# USB_SATA.net
KiCad netlist of a schematic drawn in Altium Designer
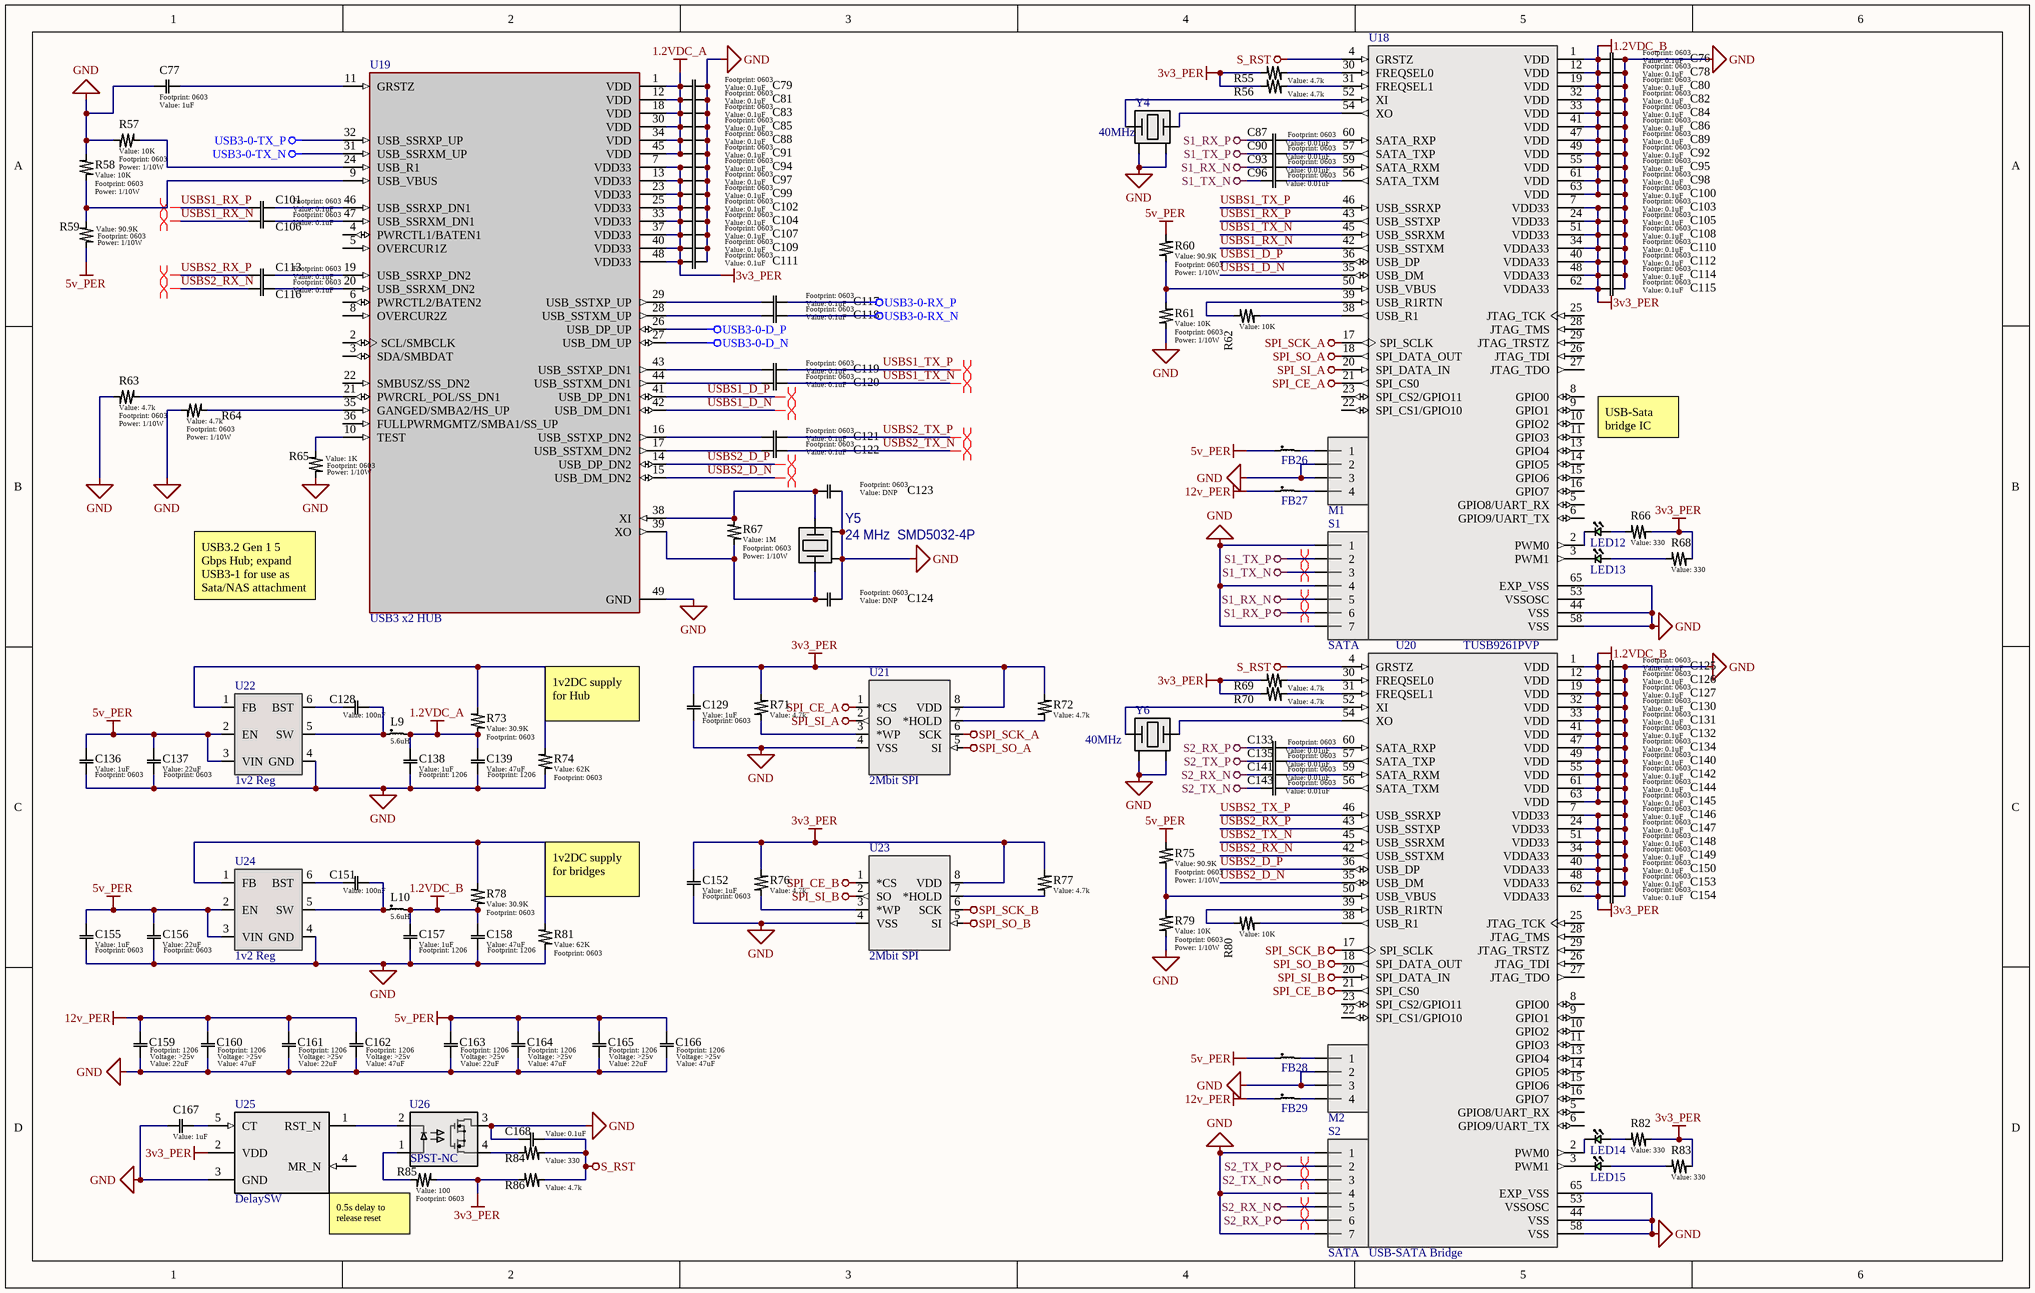
[diagram p0: USB_SATA.SchDoc]

(export (version "E")
  (design (tool "Eeschema 10.0.6"))
  (components
    (comp (ref "C76")
      (value "0.1uF")
      (footprint "0603")
      (fields
        (field (name "VOLTAGE") "10V")
        (field (name "TOLERANCE") "10%")
        (field (name "Comment") "Generic Capacitor")
      )
      (libsource (lib "Capacitors") (part "Generic Capacitor"))
    )
    (comp (ref "C77")
      (value "1uF")
      (footprint "0603")
      (fields
        (field (name "VOLTAGE") ">10V")
        (field (name "TOLERANCE") "10%")
        (field (name "Comment") "Generic Capacitor")
      )
      (libsource (lib "Capacitors") (part "Generic Capacitor"))
    )
    (comp (ref "C78")
      (value "0.1uF")
      (footprint "0603")
      (fields
        (field (name "VOLTAGE") "10V")
        (field (name "TOLERANCE") "10%")
        (field (name "Comment") "Generic Capacitor")
      )
      (libsource (lib "Capacitors") (part "Generic Capacitor"))
    )
    (comp (ref "C79")
      (value "0.1uF")
      (footprint "0603")
      (fields
        (field (name "VOLTAGE") "10V")
        (field (name "TOLERANCE") "10%")
        (field (name "Comment") "Generic Capacitor")
      )
      (libsource (lib "Capacitors") (part "Generic Capacitor"))
    )
    (comp (ref "C80")
      (value "0.1uF")
      (footprint "0603")
      (fields
        (field (name "VOLTAGE") "10V")
        (field (name "TOLERANCE") "10%")
        (field (name "Comment") "Generic Capacitor")
      )
      (libsource (lib "Capacitors") (part "Generic Capacitor"))
    )
    (comp (ref "C81")
      (value "0.1uF")
      (footprint "0603")
      (fields
        (field (name "VOLTAGE") "10V")
        (field (name "TOLERANCE") "10%")
        (field (name "Comment") "Generic Capacitor")
      )
      (libsource (lib "Capacitors") (part "Generic Capacitor"))
    )
    (comp (ref "C82")
      (value "0.1uF")
      (footprint "0603")
      (fields
        (field (name "VOLTAGE") "10V")
        (field (name "TOLERANCE") "10%")
        (field (name "Comment") "Generic Capacitor")
      )
      (libsource (lib "Capacitors") (part "Generic Capacitor"))
    )
    (comp (ref "C83")
      (value "0.1uF")
      (footprint "0603")
      (fields
        (field (name "VOLTAGE") "10V")
        (field (name "TOLERANCE") "10%")
        (field (name "Comment") "Generic Capacitor")
      )
      (libsource (lib "Capacitors") (part "Generic Capacitor"))
    )
    (comp (ref "C84")
      (value "0.1uF")
      (footprint "0603")
      (fields
        (field (name "VOLTAGE") "10V")
        (field (name "TOLERANCE") "10%")
        (field (name "Comment") "Generic Capacitor")
      )
      (libsource (lib "Capacitors") (part "Generic Capacitor"))
    )
    (comp (ref "C85")
      (value "0.1uF")
      (footprint "0603")
      (fields
        (field (name "VOLTAGE") "10V")
        (field (name "TOLERANCE") "10%")
        (field (name "Comment") "Generic Capacitor")
      )
      (libsource (lib "Capacitors") (part "Generic Capacitor"))
    )
    (comp (ref "C86")
      (value "0.1uF")
      (footprint "0603")
      (fields
        (field (name "VOLTAGE") "10V")
        (field (name "TOLERANCE") "10%")
        (field (name "Comment") "Generic Capacitor")
      )
      (libsource (lib "Capacitors") (part "Generic Capacitor"))
    )
    (comp (ref "C87")
      (value "0.01uF")
      (footprint "0603")
      (fields
        (field (name "VOLTAGE") "10V")
        (field (name "TOLERANCE") "10%")
        (field (name "Comment") "Generic Capacitor")
      )
      (libsource (lib "Capacitors") (part "Generic Capacitor"))
    )
    (comp (ref "C88")
      (value "0.1uF")
      (footprint "0603")
      (fields
        (field (name "VOLTAGE") "10V")
        (field (name "TOLERANCE") "10%")
        (field (name "Comment") "Generic Capacitor")
      )
      (libsource (lib "Capacitors") (part "Generic Capacitor"))
    )
    (comp (ref "C89")
      (value "0.1uF")
      (footprint "0603")
      (fields
        (field (name "VOLTAGE") "10V")
        (field (name "TOLERANCE") "10%")
        (field (name "Comment") "Generic Capacitor")
      )
      (libsource (lib "Capacitors") (part "Generic Capacitor"))
    )
    (comp (ref "C90")
      (value "0.01uF")
      (footprint "0603")
      (fields
        (field (name "VOLTAGE") "10V")
        (field (name "TOLERANCE") "10%")
        (field (name "Comment") "Generic Capacitor")
      )
      (libsource (lib "Capacitors") (part "Generic Capacitor"))
    )
    (comp (ref "C91")
      (value "0.1uF")
      (footprint "0603")
      (fields
        (field (name "VOLTAGE") "10V")
        (field (name "TOLERANCE") "10%")
        (field (name "Comment") "Generic Capacitor")
      )
      (libsource (lib "Capacitors") (part "Generic Capacitor"))
    )
    (comp (ref "C92")
      (value "0.1uF")
      (footprint "0603")
      (fields
        (field (name "VOLTAGE") "10V")
        (field (name "TOLERANCE") "10%")
        (field (name "Comment") "Generic Capacitor")
      )
      (libsource (lib "Capacitors") (part "Generic Capacitor"))
    )
    (comp (ref "C93")
      (value "0.01uF")
      (footprint "0603")
      (fields
        (field (name "VOLTAGE") "10V")
        (field (name "TOLERANCE") "10%")
        (field (name "Comment") "Generic Capacitor")
      )
      (libsource (lib "Capacitors") (part "Generic Capacitor"))
    )
    (comp (ref "C94")
      (value "0.1uF")
      (footprint "0603")
      (fields
        (field (name "VOLTAGE") "10V")
        (field (name "TOLERANCE") "10%")
        (field (name "Comment") "Generic Capacitor")
      )
      (libsource (lib "Capacitors") (part "Generic Capacitor"))
    )
    (comp (ref "C95")
      (value "0.1uF")
      (footprint "0603")
      (fields
        (field (name "VOLTAGE") "10V")
        (field (name "TOLERANCE") "10%")
        (field (name "Comment") "Generic Capacitor")
      )
      (libsource (lib "Capacitors") (part "Generic Capacitor"))
    )
    (comp (ref "C96")
      (value "0.01uF")
      (footprint "0603")
      (fields
        (field (name "VOLTAGE") "10V")
        (field (name "TOLERANCE") "10%")
        (field (name "Comment") "Generic Capacitor")
      )
      (libsource (lib "Capacitors") (part "Generic Capacitor"))
    )
    (comp (ref "C97")
      (value "0.1uF")
      (footprint "0603")
      (fields
        (field (name "VOLTAGE") "10V")
        (field (name "TOLERANCE") "10%")
        (field (name "Comment") "Generic Capacitor")
      )
      (libsource (lib "Capacitors") (part "Generic Capacitor"))
    )
    (comp (ref "C98")
      (value "0.1uF")
      (footprint "0603")
      (fields
        (field (name "VOLTAGE") "10V")
        (field (name "TOLERANCE") "10%")
        (field (name "Comment") "Generic Capacitor")
      )
      (libsource (lib "Capacitors") (part "Generic Capacitor"))
    )
    (comp (ref "C99")
      (value "0.1uF")
      (footprint "0603")
      (fields
        (field (name "VOLTAGE") "10V")
        (field (name "TOLERANCE") "10%")
        (field (name "Comment") "Generic Capacitor")
      )
      (libsource (lib "Capacitors") (part "Generic Capacitor"))
    )
    (comp (ref "C100")
      (value "0.1uF")
      (footprint "0603")
      (fields
        (field (name "VOLTAGE") "10V")
        (field (name "TOLERANCE") "10%")
        (field (name "Comment") "Generic Capacitor")
      )
      (libsource (lib "Capacitors") (part "Generic Capacitor"))
    )
    (comp (ref "C101")
      (value "0.1uF")
      (footprint "0603")
      (fields
        (field (name "VOLTAGE") "10V")
        (field (name "TOLERANCE") "10%")
        (field (name "Comment") "Generic Capacitor")
      )
      (libsource (lib "Capacitors") (part "Generic Capacitor"))
    )
    (comp (ref "C102")
      (value "0.1uF")
      (footprint "0603")
      (fields
        (field (name "VOLTAGE") "10V")
        (field (name "TOLERANCE") "10%")
        (field (name "Comment") "Generic Capacitor")
      )
      (libsource (lib "Capacitors") (part "Generic Capacitor"))
    )
    (comp (ref "C103")
      (value "0.1uF")
      (footprint "0603")
      (fields
        (field (name "VOLTAGE") "10V")
        (field (name "TOLERANCE") "10%")
        (field (name "Comment") "Generic Capacitor")
      )
      (libsource (lib "Capacitors") (part "Generic Capacitor"))
    )
    (comp (ref "C104")
      (value "0.1uF")
      (footprint "0603")
      (fields
        (field (name "VOLTAGE") "10V")
        (field (name "TOLERANCE") "10%")
        (field (name "Comment") "Generic Capacitor")
      )
      (libsource (lib "Capacitors") (part "Generic Capacitor"))
    )
    (comp (ref "C105")
      (value "0.1uF")
      (footprint "0603")
      (fields
        (field (name "VOLTAGE") "10V")
        (field (name "TOLERANCE") "10%")
        (field (name "Comment") "Generic Capacitor")
      )
      (libsource (lib "Capacitors") (part "Generic Capacitor"))
    )
    (comp (ref "C106")
      (value "0.1uF")
      (footprint "0603")
      (fields
        (field (name "VOLTAGE") "10V")
        (field (name "TOLERANCE") "10%")
        (field (name "Comment") "Generic Capacitor")
      )
      (libsource (lib "Capacitors") (part "Generic Capacitor"))
    )
    (comp (ref "C107")
      (value "0.1uF")
      (footprint "0603")
      (fields
        (field (name "VOLTAGE") "10V")
        (field (name "TOLERANCE") "10%")
        (field (name "Comment") "Generic Capacitor")
      )
      (libsource (lib "Capacitors") (part "Generic Capacitor"))
    )
    (comp (ref "C108")
      (value "0.1uF")
      (footprint "0603")
      (fields
        (field (name "VOLTAGE") "10V")
        (field (name "TOLERANCE") "10%")
        (field (name "Comment") "Generic Capacitor")
      )
      (libsource (lib "Capacitors") (part "Generic Capacitor"))
    )
    (comp (ref "C109")
      (value "0.1uF")
      (footprint "0603")
      (fields
        (field (name "VOLTAGE") "10V")
        (field (name "TOLERANCE") "10%")
        (field (name "Comment") "Generic Capacitor")
      )
      (libsource (lib "Capacitors") (part "Generic Capacitor"))
    )
    (comp (ref "C110")
      (value "0.1uF")
      (footprint "0603")
      (fields
        (field (name "VOLTAGE") "10V")
        (field (name "TOLERANCE") "10%")
        (field (name "Comment") "Generic Capacitor")
      )
      (libsource (lib "Capacitors") (part "Generic Capacitor"))
    )
    (comp (ref "C111")
      (value "0.1uF")
      (footprint "0603")
      (fields
        (field (name "VOLTAGE") "10V")
        (field (name "TOLERANCE") "10%")
        (field (name "Comment") "Generic Capacitor")
      )
      (libsource (lib "Capacitors") (part "Generic Capacitor"))
    )
    (comp (ref "C112")
      (value "0.1uF")
      (footprint "0603")
      (fields
        (field (name "VOLTAGE") "10V")
        (field (name "TOLERANCE") "10%")
        (field (name "Comment") "Generic Capacitor")
      )
      (libsource (lib "Capacitors") (part "Generic Capacitor"))
    )
    (comp (ref "C113")
      (value "0.1uF")
      (footprint "0603")
      (fields
        (field (name "VOLTAGE") "10V")
        (field (name "TOLERANCE") "10%")
        (field (name "Comment") "Generic Capacitor")
      )
      (libsource (lib "Capacitors") (part "Generic Capacitor"))
    )
    (comp (ref "C114")
      (value "0.1uF")
      (footprint "0603")
      (fields
        (field (name "VOLTAGE") "10V")
        (field (name "TOLERANCE") "10%")
        (field (name "Comment") "Generic Capacitor")
      )
      (libsource (lib "Capacitors") (part "Generic Capacitor"))
    )
    (comp (ref "C115")
      (value "0.1uF")
      (footprint "0603")
      (fields
        (field (name "VOLTAGE") "10V")
        (field (name "TOLERANCE") "10%")
        (field (name "Comment") "Generic Capacitor")
      )
      (libsource (lib "Capacitors") (part "Generic Capacitor"))
    )
    (comp (ref "C116")
      (value "0.1uF")
      (footprint "0603")
      (fields
        (field (name "VOLTAGE") "10V")
        (field (name "TOLERANCE") "10%")
        (field (name "Comment") "Generic Capacitor")
      )
      (libsource (lib "Capacitors") (part "Generic Capacitor"))
    )
    (comp (ref "C117")
      (value "0.1uF")
      (footprint "0603")
      (fields
        (field (name "VOLTAGE") "10V")
        (field (name "TOLERANCE") "10%")
        (field (name "Comment") "Generic Capacitor")
      )
      (libsource (lib "Capacitors") (part "Generic Capacitor"))
    )
    (comp (ref "C118")
      (value "0.1uF")
      (footprint "0603")
      (fields
        (field (name "VOLTAGE") "10V")
        (field (name "TOLERANCE") "10%")
        (field (name "Comment") "Generic Capacitor")
      )
      (libsource (lib "Capacitors") (part "Generic Capacitor"))
    )
    (comp (ref "C119")
      (value "0.1uF")
      (footprint "0603")
      (fields
        (field (name "VOLTAGE") "10V")
        (field (name "TOLERANCE") "10%")
        (field (name "Comment") "Generic Capacitor")
      )
      (libsource (lib "Capacitors") (part "Generic Capacitor"))
    )
    (comp (ref "C120")
      (value "0.1uF")
      (footprint "0603")
      (fields
        (field (name "VOLTAGE") "10V")
        (field (name "TOLERANCE") "10%")
        (field (name "Comment") "Generic Capacitor")
      )
      (libsource (lib "Capacitors") (part "Generic Capacitor"))
    )
    (comp (ref "C121")
      (value "0.1uF")
      (footprint "0603")
      (fields
        (field (name "VOLTAGE") "10V")
        (field (name "TOLERANCE") "10%")
        (field (name "Comment") "Generic Capacitor")
      )
      (libsource (lib "Capacitors") (part "Generic Capacitor"))
    )
    (comp (ref "C122")
      (value "0.1uF")
      (footprint "0603")
      (fields
        (field (name "VOLTAGE") "10V")
        (field (name "TOLERANCE") "10%")
        (field (name "Comment") "Generic Capacitor")
      )
      (libsource (lib "Capacitors") (part "Generic Capacitor"))
    )
    (comp (ref "C123")
      (value "DNP")
      (footprint "0603")
      (fields
        (field (name "VOLTAGE") ">10V")
        (field (name "TOLERANCE") "10%")
        (field (name "Comment") "Generic Capacitor")
      )
      (libsource (lib "Capacitors") (part "Generic Capacitor"))
    )
    (comp (ref "C124")
      (value "DNP")
      (footprint "0603")
      (fields
        (field (name "VOLTAGE") ">10V")
        (field (name "TOLERANCE") "10%")
        (field (name "Comment") "Generic Capacitor")
      )
      (libsource (lib "Capacitors") (part "Generic Capacitor"))
    )
    (comp (ref "C125")
      (value "0.1uF")
      (footprint "0603")
      (fields
        (field (name "VOLTAGE") "10V")
        (field (name "TOLERANCE") "10%")
        (field (name "Comment") "Generic Capacitor")
      )
      (libsource (lib "Capacitors") (part "Generic Capacitor"))
    )
    (comp (ref "C126")
      (value "0.1uF")
      (footprint "0603")
      (fields
        (field (name "VOLTAGE") "10V")
        (field (name "TOLERANCE") "10%")
        (field (name "Comment") "Generic Capacitor")
      )
      (libsource (lib "Capacitors") (part "Generic Capacitor"))
    )
    (comp (ref "C127")
      (value "0.1uF")
      (footprint "0603")
      (fields
        (field (name "VOLTAGE") "10V")
        (field (name "TOLERANCE") "10%")
        (field (name "Comment") "Generic Capacitor")
      )
      (libsource (lib "Capacitors") (part "Generic Capacitor"))
    )
    (comp (ref "C128")
      (value "100nF")
      (footprint "0603")
      (fields
        (field (name "VOLTAGE") ">10V")
        (field (name "TOLERANCE") "10%")
        (field (name "Comment") "Generic Capacitor")
      )
      (libsource (lib "Capacitors") (part "Generic Capacitor"))
    )
    (comp (ref "C129")
      (value "1uF")
      (footprint "0603")
      (fields
        (field (name "VOLTAGE") ">10V")
        (field (name "TOLERANCE") "10%")
        (field (name "Comment") "Generic Capacitor")
      )
      (libsource (lib "Capacitors") (part "Generic Capacitor"))
    )
    (comp (ref "C130")
      (value "0.1uF")
      (footprint "0603")
      (fields
        (field (name "VOLTAGE") "10V")
        (field (name "TOLERANCE") "10%")
        (field (name "Comment") "Generic Capacitor")
      )
      (libsource (lib "Capacitors") (part "Generic Capacitor"))
    )
    (comp (ref "C131")
      (value "0.1uF")
      (footprint "0603")
      (fields
        (field (name "VOLTAGE") "10V")
        (field (name "TOLERANCE") "10%")
        (field (name "Comment") "Generic Capacitor")
      )
      (libsource (lib "Capacitors") (part "Generic Capacitor"))
    )
    (comp (ref "C132")
      (value "0.1uF")
      (footprint "0603")
      (fields
        (field (name "VOLTAGE") "10V")
        (field (name "TOLERANCE") "10%")
        (field (name "Comment") "Generic Capacitor")
      )
      (libsource (lib "Capacitors") (part "Generic Capacitor"))
    )
    (comp (ref "C133")
      (value "0.01uF")
      (footprint "0603")
      (fields
        (field (name "VOLTAGE") "10V")
        (field (name "TOLERANCE") "10%")
        (field (name "Comment") "Generic Capacitor")
      )
      (libsource (lib "Capacitors") (part "Generic Capacitor"))
    )
    (comp (ref "C134")
      (value "0.1uF")
      (footprint "0603")
      (fields
        (field (name "VOLTAGE") "10V")
        (field (name "TOLERANCE") "10%")
        (field (name "Comment") "Generic Capacitor")
      )
      (libsource (lib "Capacitors") (part "Generic Capacitor"))
    )
    (comp (ref "C135")
      (value "0.01uF")
      (footprint "0603")
      (fields
        (field (name "VOLTAGE") "10V")
        (field (name "TOLERANCE") "10%")
        (field (name "Comment") "Generic Capacitor")
      )
      (libsource (lib "Capacitors") (part "Generic Capacitor"))
    )
    (comp (ref "C136")
      (value "1uF")
      (footprint "0603")
      (fields
        (field (name "VOLTAGE") ">10V")
        (field (name "TOLERANCE") "10%")
        (field (name "Comment") "Generic Capacitor")
      )
      (libsource (lib "Capacitors") (part "Generic Capacitor"))
    )
    (comp (ref "C137")
      (value "22uF")
      (footprint "0603")
      (fields
        (field (name "VOLTAGE") ">10V")
        (field (name "TOLERANCE") "10%")
        (field (name "Comment") "Generic Capacitor")
      )
      (libsource (lib "Capacitors") (part "Generic Capacitor"))
    )
    (comp (ref "C138")
      (value "1uF")
      (footprint "1206")
      (fields
        (field (name "VOLTAGE") ">10V")
        (field (name "TOLERANCE") "10%")
        (field (name "Comment") "Generic Capacitor")
      )
      (libsource (lib "Capacitors") (part "Generic Capacitor"))
    )
    (comp (ref "C139")
      (value "47uF")
      (footprint "1206")
      (fields
        (field (name "VOLTAGE") ">10V")
        (field (name "TOLERANCE") "10%")
        (field (name "Comment") "Generic Capacitor")
      )
      (libsource (lib "Capacitors") (part "Generic Capacitor"))
    )
    (comp (ref "C140")
      (value "0.1uF")
      (footprint "0603")
      (fields
        (field (name "VOLTAGE") "10V")
        (field (name "TOLERANCE") "10%")
        (field (name "Comment") "Generic Capacitor")
      )
      (libsource (lib "Capacitors") (part "Generic Capacitor"))
    )
    (comp (ref "C141")
      (value "0.01uF")
      (footprint "0603")
      (fields
        (field (name "VOLTAGE") "10V")
        (field (name "TOLERANCE") "10%")
        (field (name "Comment") "Generic Capacitor")
      )
      (libsource (lib "Capacitors") (part "Generic Capacitor"))
    )
    (comp (ref "C142")
      (value "0.1uF")
      (footprint "0603")
      (fields
        (field (name "VOLTAGE") "10V")
        (field (name "TOLERANCE") "10%")
        (field (name "Comment") "Generic Capacitor")
      )
      (libsource (lib "Capacitors") (part "Generic Capacitor"))
    )
    (comp (ref "C143")
      (value "0.01uF")
      (footprint "0603")
      (fields
        (field (name "VOLTAGE") "10V")
        (field (name "TOLERANCE") "10%")
        (field (name "Comment") "Generic Capacitor")
      )
      (libsource (lib "Capacitors") (part "Generic Capacitor"))
    )
    (comp (ref "C144")
      (value "0.1uF")
      (footprint "0603")
      (fields
        (field (name "VOLTAGE") "10V")
        (field (name "TOLERANCE") "10%")
        (field (name "Comment") "Generic Capacitor")
      )
      (libsource (lib "Capacitors") (part "Generic Capacitor"))
    )
    (comp (ref "C145")
      (value "0.1uF")
      (footprint "0603")
      (fields
        (field (name "VOLTAGE") "10V")
        (field (name "TOLERANCE") "10%")
        (field (name "Comment") "Generic Capacitor")
      )
      (libsource (lib "Capacitors") (part "Generic Capacitor"))
    )
    (comp (ref "C146")
      (value "0.1uF")
      (footprint "0603")
      (fields
        (field (name "VOLTAGE") "10V")
        (field (name "TOLERANCE") "10%")
        (field (name "Comment") "Generic Capacitor")
      )
      (libsource (lib "Capacitors") (part "Generic Capacitor"))
    )
    (comp (ref "C147")
      (value "0.1uF")
      (footprint "0603")
      (fields
        (field (name "VOLTAGE") "10V")
        (field (name "TOLERANCE") "10%")
        (field (name "Comment") "Generic Capacitor")
      )
      (libsource (lib "Capacitors") (part "Generic Capacitor"))
    )
    (comp (ref "C148")
      (value "0.1uF")
      (footprint "0603")
      (fields
        (field (name "VOLTAGE") "10V")
        (field (name "TOLERANCE") "10%")
        (field (name "Comment") "Generic Capacitor")
      )
      (libsource (lib "Capacitors") (part "Generic Capacitor"))
    )
    (comp (ref "C149")
      (value "0.1uF")
      (footprint "0603")
      (fields
        (field (name "VOLTAGE") "10V")
        (field (name "TOLERANCE") "10%")
        (field (name "Comment") "Generic Capacitor")
      )
      (libsource (lib "Capacitors") (part "Generic Capacitor"))
    )
    (comp (ref "C150")
      (value "0.1uF")
      (footprint "0603")
      (fields
        (field (name "VOLTAGE") "10V")
        (field (name "TOLERANCE") "10%")
        (field (name "Comment") "Generic Capacitor")
      )
      (libsource (lib "Capacitors") (part "Generic Capacitor"))
    )
    (comp (ref "C151")
      (value "100nF")
      (footprint "0603")
      (fields
        (field (name "VOLTAGE") ">10V")
        (field (name "TOLERANCE") "10%")
        (field (name "Comment") "Generic Capacitor")
      )
      (libsource (lib "Capacitors") (part "Generic Capacitor"))
    )
    (comp (ref "C152")
      (value "1uF")
      (footprint "0603")
      (fields
        (field (name "VOLTAGE") ">10V")
        (field (name "TOLERANCE") "10%")
        (field (name "Comment") "Generic Capacitor")
      )
      (libsource (lib "Capacitors") (part "Generic Capacitor"))
    )
    (comp (ref "C153")
      (value "0.1uF")
      (footprint "0603")
      (fields
        (field (name "VOLTAGE") "10V")
        (field (name "TOLERANCE") "10%")
        (field (name "Comment") "Generic Capacitor")
      )
      (libsource (lib "Capacitors") (part "Generic Capacitor"))
    )
    (comp (ref "C154")
      (value "0.1uF")
      (footprint "0603")
      (fields
        (field (name "VOLTAGE") "10V")
        (field (name "TOLERANCE") "10%")
        (field (name "Comment") "Generic Capacitor")
      )
      (libsource (lib "Capacitors") (part "Generic Capacitor"))
    )
    (comp (ref "C155")
      (value "1uF")
      (footprint "0603")
      (fields
        (field (name "VOLTAGE") ">10V")
        (field (name "TOLERANCE") "10%")
        (field (name "Comment") "Generic Capacitor")
      )
      (libsource (lib "Capacitors") (part "Generic Capacitor"))
    )
    (comp (ref "C156")
      (value "22uF")
      (footprint "0603")
      (fields
        (field (name "VOLTAGE") ">10V")
        (field (name "TOLERANCE") "10%")
        (field (name "Comment") "Generic Capacitor")
      )
      (libsource (lib "Capacitors") (part "Generic Capacitor"))
    )
    (comp (ref "C157")
      (value "1uF")
      (footprint "1206")
      (fields
        (field (name "VOLTAGE") ">10V")
        (field (name "TOLERANCE") "10%")
        (field (name "Comment") "Generic Capacitor")
      )
      (libsource (lib "Capacitors") (part "Generic Capacitor"))
    )
    (comp (ref "C158")
      (value "47uF")
      (footprint "1206")
      (fields
        (field (name "VOLTAGE") ">10V")
        (field (name "TOLERANCE") "10%")
        (field (name "Comment") "Generic Capacitor")
      )
      (libsource (lib "Capacitors") (part "Generic Capacitor"))
    )
    (comp (ref "C159")
      (value "22uF")
      (footprint "1206")
      (fields
        (field (name "VOLTAGE") ">25v")
        (field (name "TOLERANCE") "20%")
        (field (name "Comment") "Generic Capacitor")
      )
      (libsource (lib "Capacitors") (part "Generic Capacitor"))
    )
    (comp (ref "C160")
      (value "47uF")
      (footprint "1206")
      (fields
        (field (name "VOLTAGE") ">25v")
        (field (name "TOLERANCE") "20%")
        (field (name "Comment") "Generic Capacitor")
      )
      (libsource (lib "Capacitors") (part "Generic Capacitor"))
    )
    (comp (ref "C161")
      (value "22uF")
      (footprint "1206")
      (fields
        (field (name "VOLTAGE") ">25v")
        (field (name "TOLERANCE") "20%")
        (field (name "Comment") "Generic Capacitor")
      )
      (libsource (lib "Capacitors") (part "Generic Capacitor"))
    )
    (comp (ref "C162")
      (value "47uF")
      (footprint "1206")
      (fields
        (field (name "VOLTAGE") ">25v")
        (field (name "TOLERANCE") "20%")
        (field (name "Comment") "Generic Capacitor")
      )
      (libsource (lib "Capacitors") (part "Generic Capacitor"))
    )
    (comp (ref "C163")
      (value "22uF")
      (footprint "1206")
      (fields
        (field (name "VOLTAGE") ">25v")
        (field (name "TOLERANCE") "20%")
        (field (name "Comment") "Generic Capacitor")
      )
      (libsource (lib "Capacitors") (part "Generic Capacitor"))
    )
    (comp (ref "C164")
      (value "47uF")
      (footprint "1206")
      (fields
        (field (name "VOLTAGE") ">25v")
        (field (name "TOLERANCE") "20%")
        (field (name "Comment") "Generic Capacitor")
      )
      (libsource (lib "Capacitors") (part "Generic Capacitor"))
    )
    (comp (ref "C165")
      (value "22uF")
      (footprint "1206")
      (fields
        (field (name "VOLTAGE") ">25v")
        (field (name "TOLERANCE") "20%")
        (field (name "Comment") "Generic Capacitor")
      )
      (libsource (lib "Capacitors") (part "Generic Capacitor"))
    )
    (comp (ref "C166")
      (value "47uF")
      (footprint "1206")
      (fields
        (field (name "VOLTAGE") ">25v")
        (field (name "TOLERANCE") "20%")
        (field (name "Comment") "Generic Capacitor")
      )
      (libsource (lib "Capacitors") (part "Generic Capacitor"))
    )
    (comp (ref "C167")
      (value "1uF")
      (footprint "0603")
      (fields
        (field (name "VOLTAGE") "10V")
        (field (name "TOLERANCE") "10%")
        (field (name "Comment") "Generic Capacitor")
      )
      (libsource (lib "Capacitors") (part "Generic Capacitor"))
    )
    (comp (ref "C168")
      (value "0.1uF")
      (footprint "0603")
      (fields
        (field (name "VOLTAGE") "10V")
        (field (name "TOLERANCE") "10%")
        (field (name "Comment") "Generic Capacitor")
      )
      (libsource (lib "Capacitors") (part "Generic Capacitor"))
    )
    (comp (ref "FB26")
      (value "1206 Ferrite")
      (footprint "1206")
      (description "160 Ohms @ 100MHz 1 Power, Signal Line Ferrite Bead 1206 (3216 Metric) 6A 18mOhm")
      (libsource (lib "Inductors") (part "HI1206T161R-10"))
    )
    (comp (ref "FB27")
      (value "1206 Ferrite")
      (footprint "1206")
      (description "160 Ohms @ 100MHz 1 Power, Signal Line Ferrite Bead 1206 (3216 Metric) 6A 18mOhm")
      (libsource (lib "Inductors") (part "HI1206T161R-10"))
    )
    (comp (ref "FB28")
      (value "1206 Ferrite")
      (footprint "1206")
      (description "160 Ohms @ 100MHz 1 Power, Signal Line Ferrite Bead 1206 (3216 Metric) 6A 18mOhm")
      (libsource (lib "Inductors") (part "HI1206T161R-10"))
    )
    (comp (ref "FB29")
      (value "1206 Ferrite")
      (footprint "1206")
      (description "160 Ohms @ 100MHz 1 Power, Signal Line Ferrite Bead 1206 (3216 Metric) 6A 18mOhm")
      (libsource (lib "Inductors") (part "HI1206T161R-10"))
    )
    (comp (ref "L9")
      (value "5.6uH")
      (footprint "TMPC0402HP")
      (description "2A 5.6uH ±20% SMD Power Inductor")
      (libsource (lib "Inductors") (part "TMPC0402HP-5R6MG-Z02"))
    )
    (comp (ref "L10")
      (value "5.6uH")
      (footprint "TMPC0402HP")
      (description "2A 5.6uH ±20% SMD Power Inductor")
      (libsource (lib "Inductors") (part "TMPC0402HP-5R6MG-Z02"))
    )
    (comp (ref "LED12")
      (value "LTST-C191KGKT")
      (footprint "0603 (1608 Metric) Concave")
      (description "LED Uni-Color Green 574nm 2-Pin Chip LED T/R")
      (libsource (lib "Gamber - Johnson LLC") (part "LTST-C191KGKT"))
    )
    (comp (ref "LED13")
      (value "LTST-C191KGKT")
      (footprint "0603 (1608 Metric) Concave")
      (description "LED Uni-Color Green 574nm 2-Pin Chip LED T/R")
      (libsource (lib "Gamber - Johnson LLC") (part "LTST-C191KGKT"))
    )
    (comp (ref "LED14")
      (value "LTST-C191KGKT")
      (footprint "0603 (1608 Metric) Concave")
      (description "LED Uni-Color Green 574nm 2-Pin Chip LED T/R")
      (libsource (lib "Gamber - Johnson LLC") (part "LTST-C191KGKT"))
    )
    (comp (ref "LED15")
      (value "LTST-C191KGKT")
      (footprint "0603 (1608 Metric) Concave")
      (description "LED Uni-Color Green 574nm 2-Pin Chip LED T/R")
      (libsource (lib "Gamber - Johnson LLC") (part "LTST-C191KGKT"))
    )
    (comp (ref "M1")
      (value "MATE-n-Lock")
      (footprint "794287-1")
      (description "4 Position Header Connector 0.200\" (5.08mm) Through Hole Tin")
      (libsource (lib "Connectors") (part "794287-1"))
    )
    (comp (ref "M2")
      (value "MATE-n-Lock")
      (footprint "794287-1")
      (description "4 Position Header Connector 0.200\" (5.08mm) Through Hole Tin")
      (libsource (lib "Connectors") (part "794287-1"))
    )
    (comp (ref "R55")
      (value "4.7k")
      (footprint "0603")
      (fields
        (field (name "TOLERANCE") "1%")
        (field (name "POWER") "1/10W")
        (field (name "Comment") "Generic Resistor")
      )
      (libsource (lib "Resistors") (part "Generic Resistor"))
    )
    (comp (ref "R56")
      (value "4.7k")
      (footprint "0603")
      (fields
        (field (name "TOLERANCE") "1%")
        (field (name "POWER") "1/10W")
        (field (name "Comment") "Generic Resistor")
      )
      (libsource (lib "Resistors") (part "Generic Resistor"))
    )
    (comp (ref "R57")
      (value "10K")
      (footprint "0603")
      (fields
        (field (name "TOLERANCE") "1%")
        (field (name "POWER") "1/10W")
        (field (name "Comment") "Generic Resistor")
      )
      (libsource (lib "Resistors") (part "Generic Resistor"))
    )
    (comp (ref "R58")
      (value "10K")
      (footprint "0603")
      (fields
        (field (name "TOLERANCE") "1%")
        (field (name "POWER") "1/10W")
        (field (name "Comment") "Generic Resistor")
      )
      (libsource (lib "Resistors") (part "Generic Resistor"))
    )
    (comp (ref "R59")
      (value "90.9K")
      (footprint "0603")
      (fields
        (field (name "TOLERANCE") "1%")
        (field (name "POWER") "1/10W")
        (field (name "Comment") "Generic Resistor")
      )
      (libsource (lib "Resistors") (part "Generic Resistor"))
    )
    (comp (ref "R60")
      (value "90.9K")
      (footprint "0603")
      (fields
        (field (name "TOLERANCE") "1%")
        (field (name "POWER") "1/10W")
        (field (name "Comment") "Generic Resistor")
      )
      (libsource (lib "Resistors") (part "Generic Resistor"))
    )
    (comp (ref "R61")
      (value "10K")
      (footprint "0603")
      (fields
        (field (name "TOLERANCE") "1%")
        (field (name "POWER") "1/10W")
        (field (name "Comment") "Generic Resistor")
      )
      (libsource (lib "Resistors") (part "Generic Resistor"))
    )
    (comp (ref "R62")
      (value "10K")
      (footprint "0603")
      (fields
        (field (name "TOLERANCE") "1%")
        (field (name "POWER") "1/10W")
        (field (name "Comment") "Generic Resistor")
      )
      (libsource (lib "Resistors") (part "Generic Resistor"))
    )
    (comp (ref "R63")
      (value "4.7k")
      (footprint "0603")
      (fields
        (field (name "TOLERANCE") "1%")
        (field (name "POWER") "1/10W")
        (field (name "Comment") "Generic Resistor")
      )
      (libsource (lib "Resistors") (part "Generic Resistor"))
    )
    (comp (ref "R64")
      (value "4.7k")
      (footprint "0603")
      (fields
        (field (name "TOLERANCE") "1%")
        (field (name "POWER") "1/10W")
        (field (name "Comment") "Generic Resistor")
      )
      (libsource (lib "Resistors") (part "Generic Resistor"))
    )
    (comp (ref "R65")
      (value "1K")
      (footprint "0603")
      (fields
        (field (name "TOLERANCE") "1%")
        (field (name "POWER") "1/10W")
        (field (name "Comment") "Generic Resistor")
      )
      (libsource (lib "Resistors") (part "Generic Resistor"))
    )
    (comp (ref "R66")
      (value "330")
      (footprint "0603")
      (fields
        (field (name "TOLERANCE") "1%")
        (field (name "POWER") "1/10W")
        (field (name "Comment") "Generic Resistor")
      )
      (libsource (lib "Resistors") (part "Generic Resistor"))
    )
    (comp (ref "R67")
      (value "1M")
      (footprint "0603")
      (fields
        (field (name "TOLERANCE") "1%")
        (field (name "POWER") "1/10W")
        (field (name "Comment") "Generic Resistor")
      )
      (libsource (lib "Resistors") (part "Generic Resistor"))
    )
    (comp (ref "R68")
      (value "330")
      (footprint "0603")
      (fields
        (field (name "TOLERANCE") "1%")
        (field (name "POWER") "1/10W")
        (field (name "Comment") "Generic Resistor")
      )
      (libsource (lib "Resistors") (part "Generic Resistor"))
    )
    (comp (ref "R69")
      (value "4.7k")
      (footprint "0603")
      (fields
        (field (name "TOLERANCE") "1%")
        (field (name "POWER") "1/10W")
        (field (name "Comment") "Generic Resistor")
      )
      (libsource (lib "Resistors") (part "Generic Resistor"))
    )
    (comp (ref "R70")
      (value "4.7k")
      (footprint "0603")
      (fields
        (field (name "TOLERANCE") "1%")
        (field (name "POWER") "1/10W")
        (field (name "Comment") "Generic Resistor")
      )
      (libsource (lib "Resistors") (part "Generic Resistor"))
    )
    (comp (ref "R71")
      (value "4.7k")
      (footprint "0603")
      (fields
        (field (name "TOLERANCE") "1%")
        (field (name "POWER") "1/10W")
        (field (name "Comment") "Generic Resistor")
      )
      (libsource (lib "Resistors") (part "Generic Resistor"))
    )
    (comp (ref "R72")
      (value "4.7k")
      (footprint "0603")
      (fields
        (field (name "TOLERANCE") "1%")
        (field (name "POWER") "1/10W")
        (field (name "Comment") "Generic Resistor")
      )
      (libsource (lib "Resistors") (part "Generic Resistor"))
    )
    (comp (ref "R73")
      (value "30.9K")
      (footprint "0603")
      (fields
        (field (name "TOLERANCE") "1%")
        (field (name "POWER") "1/10W")
        (field (name "Comment") "Generic Resistor")
      )
      (libsource (lib "Resistors") (part "Generic Resistor"))
    )
    (comp (ref "R74")
      (value "62K")
      (footprint "0603")
      (fields
        (field (name "TOLERANCE") "1%")
        (field (name "POWER") "1/10W")
        (field (name "Comment") "Generic Resistor")
      )
      (libsource (lib "Resistors") (part "Generic Resistor"))
    )
    (comp (ref "R75")
      (value "90.9K")
      (footprint "0603")
      (fields
        (field (name "TOLERANCE") "1%")
        (field (name "POWER") "1/10W")
        (field (name "Comment") "Generic Resistor")
      )
      (libsource (lib "Resistors") (part "Generic Resistor"))
    )
    (comp (ref "R76")
      (value "4.7k")
      (footprint "0603")
      (fields
        (field (name "TOLERANCE") "1%")
        (field (name "POWER") "1/10W")
        (field (name "Comment") "Generic Resistor")
      )
      (libsource (lib "Resistors") (part "Generic Resistor"))
    )
    (comp (ref "R77")
      (value "4.7k")
      (footprint "0603")
      (fields
        (field (name "TOLERANCE") "1%")
        (field (name "POWER") "1/10W")
        (field (name "Comment") "Generic Resistor")
      )
      (libsource (lib "Resistors") (part "Generic Resistor"))
    )
    (comp (ref "R78")
      (value "30.9K")
      (footprint "0603")
      (fields
        (field (name "TOLERANCE") "1%")
        (field (name "POWER") "1/10W")
        (field (name "Comment") "Generic Resistor")
      )
      (libsource (lib "Resistors") (part "Generic Resistor"))
    )
    (comp (ref "R79")
      (value "10K")
      (footprint "0603")
      (fields
        (field (name "TOLERANCE") "1%")
        (field (name "POWER") "1/10W")
        (field (name "Comment") "Generic Resistor")
      )
      (libsource (lib "Resistors") (part "Generic Resistor"))
    )
    (comp (ref "R80")
      (value "10K")
      (footprint "0603")
      (fields
        (field (name "TOLERANCE") "1%")
        (field (name "POWER") "1/10W")
        (field (name "Comment") "Generic Resistor")
      )
      (libsource (lib "Resistors") (part "Generic Resistor"))
    )
    (comp (ref "R81")
      (value "62K")
      (footprint "0603")
      (fields
        (field (name "TOLERANCE") "1%")
        (field (name "POWER") "1/10W")
        (field (name "Comment") "Generic Resistor")
      )
      (libsource (lib "Resistors") (part "Generic Resistor"))
    )
    (comp (ref "R82")
      (value "330")
      (footprint "0603")
      (fields
        (field (name "TOLERANCE") "1%")
        (field (name "POWER") "1/10W")
        (field (name "Comment") "Generic Resistor")
      )
      (libsource (lib "Resistors") (part "Generic Resistor"))
    )
    (comp (ref "R83")
      (value "330")
      (footprint "0603")
      (fields
        (field (name "TOLERANCE") "1%")
        (field (name "POWER") "1/10W")
        (field (name "Comment") "Generic Resistor")
      )
      (libsource (lib "Resistors") (part "Generic Resistor"))
    )
    (comp (ref "R84")
      (value "330")
      (footprint "0603")
      (fields
        (field (name "TOLERANCE") "1%")
        (field (name "POWER") "1/10W")
        (field (name "Comment") "Generic Resistor")
      )
      (libsource (lib "Resistors") (part "Generic Resistor"))
    )
    (comp (ref "R85")
      (value "100")
      (footprint "0603")
      (fields
        (field (name "TOLERANCE") "1%")
        (field (name "POWER") "1/10W")
        (field (name "Comment") "Generic Resistor")
      )
      (libsource (lib "Resistors") (part "Generic Resistor"))
    )
    (comp (ref "R86")
      (value "4.7k")
      (footprint "0603")
      (fields
        (field (name "TOLERANCE") "1%")
        (field (name "POWER") "1/10W")
        (field (name "Comment") "Generic Resistor")
      )
      (libsource (lib "Resistors") (part "Generic Resistor"))
    )
    (comp (ref "S1")
      (value "SATA")
      (footprint "67800-8025")
      (description "7 Position SATA Header, Shrouded Connector Solder Through Hole")
      (libsource (lib "Connectors") (part "67800-8025"))
    )
    (comp (ref "S2")
      (value "SATA")
      (footprint "67800-8025")
      (description "7 Position SATA Header, Shrouded Connector Solder Through Hole")
      (libsource (lib "Connectors") (part "67800-8025"))
    )
    (comp (ref "U18")
      (value "USB-SATA Bridge")
      (footprint "64-HTQFP (7x7)")
      (description "HDD, CD, DVD Drive Interface 64-HTQFP _7x7_")
      (fields
        (field (name "MF") "Texas Instruments")
        (field (name "DIGI-KEY_PART_NUMBER") "296-28827-ND")
        (field (name "MP") "TUSB9261PVP")
      )
      (libsource (lib "Misc ICs") (part "TUSB9261PVP"))
    )
    (comp (ref "U19")
      (value "USB3 x2 HUB")
      (footprint "HTQFP-48(7x7)")
      (description "USB Hub Controller USB 3.0")
      (libsource (lib "Hub ICs") (part "TUSB8020BPHP"))
    )
    (comp (ref "U20")
      (value "USB-SATA Bridge")
      (footprint "64-HTQFP (7x7)")
      (description "HDD, CD, DVD Drive Interface 64-HTQFP _7x7_")
      (fields (field (name "MF") "Texas Instruments") (field (name "DIGI-KEY_PART_NUMBER") "296-28827-ND"))
      (libsource (lib "Misc ICs") (part "TUSB9261PVP"))
    )
    (comp (ref "U21")
      (value "2Mbit SPI")
      (footprint "8-SOIC (0.154\", 3.90mm Width)")
      (description "IC FLASH 2MBIT SPI 30MHZ 8SOP")
      (libsource (lib "Misc ICs") (part "LE25U20AMB-AH"))
    )
    (comp (ref "U22")
      (value "1v2 Reg")
      (footprint "TSOT-23-6")
      (description "Step-down type Adjustable 2A 1.2V~12V 3.8V~32V TSOT-23-6 DC-DC Converter")
      (libsource (lib "Regulators") (part "AP63201WU-7"))
    )
    (comp (ref "U23")
      (value "2Mbit SPI")
      (footprint "8-SOIC (0.154\", 3.90mm Width)")
      (description "IC FLASH 2MBIT SPI 30MHZ 8SOP")
      (libsource (lib "Misc ICs") (part "LE25U20AMB-AH"))
    )
    (comp (ref "U24")
      (value "1v2 Reg")
      (footprint "TSOT-23-6")
      (description "Step-down type Adjustable 2A 1.2V~12V 3.8V~32V TSOT-23-6 DC-DC Converter")
      (libsource (lib "Regulators") (part "AP63201WU-7"))
    )
    (comp (ref "U25")
      (value "DelaySW")
      (footprint "TSOT-23-5")
      (description "Supervisor Open Drain or Open Collector 1 Channel SOT-23-5\r\n2.2V Threshold")
      (libsource (lib "Switches") (part "TPS3840DL22DBVR"))
    )
    (comp (ref "U26")
      (value "SPST-NC")
      (footprint "4-SOP")
      (description "SSR RELAY SPST-NC 400MA 0-60V")
      (libsource (lib "Switches") (part "CPC1117N"))
    )
    (comp (ref "Y4")
      (value "40MHz")
      (footprint "SMD3225-4P")
      (description "40MHz Surface Mount Crystal 10pF ±10ppm SMD3225-4P Crystal")
      (libsource (lib "Clock ICs") (part "L327S400H11L"))
    )
    (comp (ref "Y5")
      (value "24 MHz  SMD5032-4P")
      (footprint "ECS-240-18-30BQ-DS")
      (description "24 MHz ±30ppm Crystal 18pF 30 Ohms 4-SMD, No Lead")
      (libsource (lib "Gamber - Johnson LLC") (part "ECS-240-18-30BQ-DS"))
    )
    (comp (ref "Y6")
      (value "40MHz")
      (footprint "SMD3225-4P")
      (description "40MHz Surface Mount Crystal 10pF ±10ppm SMD3225-4P Crystal")
      (libsource (lib "Clock ICs") (part "L327S400H11L"))
    )
  )
  (nets
    (net (code "1") (name "/USBS1_D_N") (class "Default")
      (node (ref "U18") (pin "35") (pinfunction "USB_DM_35") (pintype "bidirectional"))
      (node (ref "U19") (pin "42") (pinfunction "USB_DM_DN1_42") (pintype "bidirectional"))
    )
    (net (code "2") (name "/USBS1_D_P") (class "Default")
      (node (ref "U18") (pin "36") (pinfunction "USB_DP_36") (pintype "bidirectional"))
      (node (ref "U19") (pin "41") (pinfunction "USB_DP_DN1_41") (pintype "bidirectional"))
    )
    (net (code "3") (name "/USBS1_RX_N") (class "Default")
      (node (ref "C106") (pin "2") (pinfunction "2_2") (pintype "passive"))
      (node (ref "U18") (pin "42") (pinfunction "USB_SSTXM_42") (pintype "output"))
    )
    (net (code "4") (name "/USBS1_RX_P") (class "Default")
      (node (ref "C101") (pin "2") (pinfunction "2_2") (pintype "passive"))
      (node (ref "U18") (pin "43") (pinfunction "USB_SSTXP_43") (pintype "output"))
    )
    (net (code "5") (name "/USBS1_TX_N") (class "Default")
      (node (ref "C120") (pin "1") (pinfunction "1_1") (pintype "passive"))
      (node (ref "U18") (pin "45") (pinfunction "USB_SSRXM_45") (pintype "input"))
    )
    (net (code "6") (name "/USBS1_TX_P") (class "Default")
      (node (ref "C119") (pin "1") (pinfunction "1_1") (pintype "passive"))
      (node (ref "U18") (pin "46") (pinfunction "USB_SSRXP_46") (pintype "input"))
    )
    (net (code "7") (name "/USBS2_D_N") (class "Default")
      (node (ref "U19") (pin "15") (pinfunction "USB_DM_DN2_15") (pintype "bidirectional"))
      (node (ref "U20") (pin "35") (pinfunction "USB_DM_35") (pintype "bidirectional"))
    )
    (net (code "8") (name "/USBS2_D_P") (class "Default")
      (node (ref "U19") (pin "14") (pinfunction "USB_DP_DN2_14") (pintype "bidirectional"))
      (node (ref "U20") (pin "36") (pinfunction "USB_DP_36") (pintype "bidirectional"))
    )
    (net (code "9") (name "/USBS2_RX_N") (class "Default")
      (node (ref "C116") (pin "2") (pinfunction "2_2") (pintype "passive"))
      (node (ref "U20") (pin "42") (pinfunction "USB_SSTXM_42") (pintype "output"))
    )
    (net (code "10") (name "/USBS2_RX_P") (class "Default")
      (node (ref "C113") (pin "2") (pinfunction "2_2") (pintype "passive"))
      (node (ref "U20") (pin "43") (pinfunction "USB_SSTXP_43") (pintype "output"))
    )
    (net (code "11") (name "/USBS2_TX_N") (class "Default")
      (node (ref "C122") (pin "1") (pinfunction "1_1") (pintype "passive"))
      (node (ref "U20") (pin "45") (pinfunction "USB_SSRXM_45") (pintype "input"))
    )
    (net (code "12") (name "/USBS2_TX_P") (class "Default")
      (node (ref "C121") (pin "1") (pinfunction "1_1") (pintype "passive"))
      (node (ref "U20") (pin "46") (pinfunction "USB_SSRXP_46") (pintype "input"))
    )
    (net (code "13") (name "1.2VDC_A") (class "Default")
      (node (ref "C138") (pin "1") (pinfunction "1_1") (pintype "passive"))
      (node (ref "C139") (pin "1") (pinfunction "1_1") (pintype "passive"))
      (node (ref "C79") (pin "2") (pinfunction "2_2") (pintype "passive"))
      (node (ref "C81") (pin "2") (pinfunction "2_2") (pintype "passive"))
      (node (ref "C83") (pin "2") (pinfunction "2_2") (pintype "passive"))
      (node (ref "C85") (pin "2") (pinfunction "2_2") (pintype "passive"))
      (node (ref "C88") (pin "2") (pinfunction "2_2") (pintype "passive"))
      (node (ref "C91") (pin "2") (pinfunction "2_2") (pintype "passive"))
      (node (ref "L9") (pin "2") (pinfunction "2_2") (pintype "passive"))
      (node (ref "R73") (pin "1") (pinfunction "1_1") (pintype "passive"))
      (node (ref "U19") (pin "1") (pinfunction "VDD_1") (pintype "power_in"))
      (node (ref "U19") (pin "12") (pinfunction "VDD_12") (pintype "power_in"))
      (node (ref "U19") (pin "18") (pinfunction "VDD_18") (pintype "power_in"))
      (node (ref "U19") (pin "30") (pinfunction "VDD_30") (pintype "power_in"))
      (node (ref "U19") (pin "34") (pinfunction "VDD_34") (pintype "power_in"))
      (node (ref "U19") (pin "45") (pinfunction "VDD_45") (pintype "power_in"))
    )
    (net (code "14") (name "1.2VDC_B") (class "Default")
      (node (ref "C100") (pin "2") (pinfunction "2_2") (pintype "passive"))
      (node (ref "C125") (pin "2") (pinfunction "2_2") (pintype "passive"))
      (node (ref "C126") (pin "2") (pinfunction "2_2") (pintype "passive"))
      (node (ref "C127") (pin "2") (pinfunction "2_2") (pintype "passive"))
      (node (ref "C130") (pin "2") (pinfunction "2_2") (pintype "passive"))
      (node (ref "C131") (pin "2") (pinfunction "2_2") (pintype "passive"))
      (node (ref "C132") (pin "2") (pinfunction "2_2") (pintype "passive"))
      (node (ref "C134") (pin "2") (pinfunction "2_2") (pintype "passive"))
      (node (ref "C140") (pin "2") (pinfunction "2_2") (pintype "passive"))
      (node (ref "C142") (pin "2") (pinfunction "2_2") (pintype "passive"))
      (node (ref "C144") (pin "2") (pinfunction "2_2") (pintype "passive"))
      (node (ref "C145") (pin "2") (pinfunction "2_2") (pintype "passive"))
      (node (ref "C157") (pin "1") (pinfunction "1_1") (pintype "passive"))
      (node (ref "C158") (pin "1") (pinfunction "1_1") (pintype "passive"))
      (node (ref "C76") (pin "2") (pinfunction "2_2") (pintype "passive"))
      (node (ref "C78") (pin "2") (pinfunction "2_2") (pintype "passive"))
      (node (ref "C80") (pin "2") (pinfunction "2_2") (pintype "passive"))
      (node (ref "C82") (pin "2") (pinfunction "2_2") (pintype "passive"))
      (node (ref "C84") (pin "2") (pinfunction "2_2") (pintype "passive"))
      (node (ref "C86") (pin "2") (pinfunction "2_2") (pintype "passive"))
      (node (ref "C89") (pin "2") (pinfunction "2_2") (pintype "passive"))
      (node (ref "C92") (pin "2") (pinfunction "2_2") (pintype "passive"))
      (node (ref "C95") (pin "2") (pinfunction "2_2") (pintype "passive"))
      (node (ref "C98") (pin "2") (pinfunction "2_2") (pintype "passive"))
      (node (ref "L10") (pin "2") (pinfunction "2_2") (pintype "passive"))
      (node (ref "R78") (pin "1") (pinfunction "1_1") (pintype "passive"))
      (node (ref "U18") (pin "1") (pinfunction "VDD_1") (pintype "power_in"))
      (node (ref "U18") (pin "12") (pinfunction "VDD_12") (pintype "power_in"))
      (node (ref "U18") (pin "19") (pinfunction "VDD_19") (pintype "power_in"))
      (node (ref "U18") (pin "32") (pinfunction "VDD_32") (pintype "power_in"))
      (node (ref "U18") (pin "33") (pinfunction "VDD_33") (pintype "power_in"))
      (node (ref "U18") (pin "41") (pinfunction "VDD_41") (pintype "power_in"))
      (node (ref "U18") (pin "47") (pinfunction "VDD_47") (pintype "power_in"))
      (node (ref "U18") (pin "49") (pinfunction "VDD_49") (pintype "power_in"))
      (node (ref "U18") (pin "55") (pinfunction "VDD_55") (pintype "power_in"))
      (node (ref "U18") (pin "61") (pinfunction "VDD_61") (pintype "power_in"))
      (node (ref "U18") (pin "63") (pinfunction "VDD_63") (pintype "power_in"))
      (node (ref "U20") (pin "1") (pinfunction "VDD_1") (pintype "power_in"))
      (node (ref "U20") (pin "12") (pinfunction "VDD_12") (pintype "power_in"))
      (node (ref "U20") (pin "19") (pinfunction "VDD_19") (pintype "power_in"))
      (node (ref "U20") (pin "32") (pinfunction "VDD_32") (pintype "power_in"))
      (node (ref "U20") (pin "33") (pinfunction "VDD_33") (pintype "power_in"))
      (node (ref "U20") (pin "41") (pinfunction "VDD_41") (pintype "power_in"))
      (node (ref "U20") (pin "47") (pinfunction "VDD_47") (pintype "power_in"))
      (node (ref "U20") (pin "49") (pinfunction "VDD_49") (pintype "power_in"))
      (node (ref "U20") (pin "55") (pinfunction "VDD_55") (pintype "power_in"))
      (node (ref "U20") (pin "61") (pinfunction "VDD_61") (pintype "power_in"))
      (node (ref "U20") (pin "63") (pinfunction "VDD_63") (pintype "power_in"))
    )
    (net (code "15") (name "3v3_PER") (class "Default")
      (node (ref "C102") (pin "2") (pinfunction "2_2") (pintype "passive"))
      (node (ref "C103") (pin "2") (pinfunction "2_2") (pintype "passive"))
      (node (ref "C104") (pin "2") (pinfunction "2_2") (pintype "passive"))
      (node (ref "C105") (pin "2") (pinfunction "2_2") (pintype "passive"))
      (node (ref "C107") (pin "2") (pinfunction "2_2") (pintype "passive"))
      (node (ref "C108") (pin "2") (pinfunction "2_2") (pintype "passive"))
      (node (ref "C109") (pin "2") (pinfunction "2_2") (pintype "passive"))
      (node (ref "C110") (pin "2") (pinfunction "2_2") (pintype "passive"))
      (node (ref "C111") (pin "2") (pinfunction "2_2") (pintype "passive"))
      (node (ref "C112") (pin "2") (pinfunction "2_2") (pintype "passive"))
      (node (ref "C114") (pin "2") (pinfunction "2_2") (pintype "passive"))
      (node (ref "C115") (pin "2") (pinfunction "2_2") (pintype "passive"))
      (node (ref "C129") (pin "1") (pinfunction "1_1") (pintype "passive"))
      (node (ref "C146") (pin "2") (pinfunction "2_2") (pintype "passive"))
      (node (ref "C147") (pin "2") (pinfunction "2_2") (pintype "passive"))
      (node (ref "C148") (pin "2") (pinfunction "2_2") (pintype "passive"))
      (node (ref "C149") (pin "2") (pinfunction "2_2") (pintype "passive"))
      (node (ref "C150") (pin "2") (pinfunction "2_2") (pintype "passive"))
      (node (ref "C152") (pin "1") (pinfunction "1_1") (pintype "passive"))
      (node (ref "C153") (pin "2") (pinfunction "2_2") (pintype "passive"))
      (node (ref "C154") (pin "2") (pinfunction "2_2") (pintype "passive"))
      (node (ref "C94") (pin "2") (pinfunction "2_2") (pintype "passive"))
      (node (ref "C97") (pin "2") (pinfunction "2_2") (pintype "passive"))
      (node (ref "C99") (pin "2") (pinfunction "2_2") (pintype "passive"))
      (node (ref "R55") (pin "1") (pinfunction "1_1") (pintype "passive"))
      (node (ref "R56") (pin "1") (pinfunction "1_1") (pintype "passive"))
      (node (ref "R66") (pin "2") (pinfunction "2_2") (pintype "passive"))
      (node (ref "R68") (pin "2") (pinfunction "2_2") (pintype "passive"))
      (node (ref "R69") (pin "1") (pinfunction "1_1") (pintype "passive"))
      (node (ref "R70") (pin "1") (pinfunction "1_1") (pintype "passive"))
      (node (ref "R71") (pin "1") (pinfunction "1_1") (pintype "passive"))
      (node (ref "R72") (pin "1") (pinfunction "1_1") (pintype "passive"))
      (node (ref "R76") (pin "1") (pinfunction "1_1") (pintype "passive"))
      (node (ref "R77") (pin "1") (pinfunction "1_1") (pintype "passive"))
      (node (ref "R82") (pin "2") (pinfunction "2_2") (pintype "passive"))
      (node (ref "R83") (pin "2") (pinfunction "2_2") (pintype "passive"))
      (node (ref "R85") (pin "2") (pinfunction "2_2") (pintype "passive"))
      (node (ref "R86") (pin "1") (pinfunction "1_1") (pintype "passive"))
      (node (ref "U18") (pin "24") (pinfunction "VDD33_24") (pintype "power_in"))
      (node (ref "U18") (pin "34") (pinfunction "VDDA33_34") (pintype "power_in"))
      (node (ref "U18") (pin "40") (pinfunction "VDDA33_40") (pintype "power_in"))
      (node (ref "U18") (pin "48") (pinfunction "VDDA33_48") (pintype "power_in"))
      (node (ref "U18") (pin "51") (pinfunction "VDD33_51") (pintype "power_in"))
      (node (ref "U18") (pin "62") (pinfunction "VDDA33_62") (pintype "power_in"))
      (node (ref "U18") (pin "7") (pinfunction "VDD33_7") (pintype "power_in"))
      (node (ref "U19") (pin "13") (pinfunction "VDD33_13") (pintype "power_in"))
      (node (ref "U19") (pin "23") (pinfunction "VDD33_23") (pintype "power_in"))
      (node (ref "U19") (pin "25") (pinfunction "VDD33_25") (pintype "power_in"))
      (node (ref "U19") (pin "33") (pinfunction "VDD33_33") (pintype "power_in"))
      (node (ref "U19") (pin "37") (pinfunction "VDD33_37") (pintype "power_in"))
      (node (ref "U19") (pin "40") (pinfunction "VDD33_40") (pintype "power_in"))
      (node (ref "U19") (pin "48") (pinfunction "VDD33_48") (pintype "power_in"))
      (node (ref "U19") (pin "7") (pinfunction "VDD33_7") (pintype "power_in"))
      (node (ref "U20") (pin "24") (pinfunction "VDD33_24") (pintype "power_in"))
      (node (ref "U20") (pin "34") (pinfunction "VDDA33_34") (pintype "power_in"))
      (node (ref "U20") (pin "40") (pinfunction "VDDA33_40") (pintype "power_in"))
      (node (ref "U20") (pin "48") (pinfunction "VDDA33_48") (pintype "power_in"))
      (node (ref "U20") (pin "51") (pinfunction "VDD33_51") (pintype "power_in"))
      (node (ref "U20") (pin "62") (pinfunction "VDDA33_62") (pintype "power_in"))
      (node (ref "U20") (pin "7") (pinfunction "VDD33_7") (pintype "power_in"))
      (node (ref "U21") (pin "8") (pinfunction "VDD_8") (pintype "power_in"))
      (node (ref "U23") (pin "8") (pinfunction "VDD_8") (pintype "power_in"))
      (node (ref "U25") (pin "2") (pinfunction "VDD_2") (pintype "power_in"))
    )
    (net (code "16") (name "5v_PER") (class "Default")
      (node (ref "C136") (pin "1") (pinfunction "1_1") (pintype "passive"))
      (node (ref "C137") (pin "1") (pinfunction "1_1") (pintype "passive"))
      (node (ref "C155") (pin "1") (pinfunction "1_1") (pintype "passive"))
      (node (ref "C156") (pin "1") (pinfunction "1_1") (pintype "passive"))
      (node (ref "C163") (pin "1") (pinfunction "1_1") (pintype "passive"))
      (node (ref "C164") (pin "1") (pinfunction "1_1") (pintype "passive"))
      (node (ref "C165") (pin "1") (pinfunction "1_1") (pintype "passive"))
      (node (ref "C166") (pin "1") (pinfunction "1_1") (pintype "passive"))
      (node (ref "FB26") (pin "1") (pinfunction "1_1") (pintype "passive"))
      (node (ref "FB28") (pin "1") (pinfunction "1_1") (pintype "passive"))
      (node (ref "R59") (pin "1") (pinfunction "1_1") (pintype "passive"))
      (node (ref "R60") (pin "1") (pinfunction "1_1") (pintype "passive"))
      (node (ref "R75") (pin "1") (pinfunction "1_1") (pintype "passive"))
      (node (ref "U22") (pin "2") (pinfunction "EN_2") (pintype "passive"))
      (node (ref "U22") (pin "3") (pinfunction "VIN_3") (pintype "passive"))
      (node (ref "U24") (pin "2") (pinfunction "EN_2") (pintype "passive"))
      (node (ref "U24") (pin "3") (pinfunction "VIN_3") (pintype "passive"))
    )
    (net (code "17") (name "12v_PER") (class "Default")
      (node (ref "C159") (pin "1") (pinfunction "1_1") (pintype "passive"))
      (node (ref "C160") (pin "1") (pinfunction "1_1") (pintype "passive"))
      (node (ref "C161") (pin "1") (pinfunction "1_1") (pintype "passive"))
      (node (ref "C162") (pin "1") (pinfunction "1_1") (pintype "passive"))
      (node (ref "FB27") (pin "1") (pinfunction "1_1") (pintype "passive"))
      (node (ref "FB29") (pin "1") (pinfunction "1_1") (pintype "passive"))
    )
    (net (code "18") (name "GND") (class "Default")
      (node (ref "C100") (pin "1") (pinfunction "1_1") (pintype "passive"))
      (node (ref "C102") (pin "1") (pinfunction "1_1") (pintype "passive"))
      (node (ref "C103") (pin "1") (pinfunction "1_1") (pintype "passive"))
      (node (ref "C104") (pin "1") (pinfunction "1_1") (pintype "passive"))
      (node (ref "C105") (pin "1") (pinfunction "1_1") (pintype "passive"))
      (node (ref "C107") (pin "1") (pinfunction "1_1") (pintype "passive"))
      (node (ref "C108") (pin "1") (pinfunction "1_1") (pintype "passive"))
      (node (ref "C109") (pin "1") (pinfunction "1_1") (pintype "passive"))
      (node (ref "C110") (pin "1") (pinfunction "1_1") (pintype "passive"))
      (node (ref "C111") (pin "1") (pinfunction "1_1") (pintype "passive"))
      (node (ref "C112") (pin "1") (pinfunction "1_1") (pintype "passive"))
      (node (ref "C114") (pin "1") (pinfunction "1_1") (pintype "passive"))
      (node (ref "C115") (pin "1") (pinfunction "1_1") (pintype "passive"))
      (node (ref "C123") (pin "1") (pinfunction "1_1") (pintype "passive"))
      (node (ref "C124") (pin "1") (pinfunction "1_1") (pintype "passive"))
      (node (ref "C125") (pin "1") (pinfunction "1_1") (pintype "passive"))
      (node (ref "C126") (pin "1") (pinfunction "1_1") (pintype "passive"))
      (node (ref "C127") (pin "1") (pinfunction "1_1") (pintype "passive"))
      (node (ref "C129") (pin "2") (pinfunction "2_2") (pintype "passive"))
      (node (ref "C130") (pin "1") (pinfunction "1_1") (pintype "passive"))
      (node (ref "C131") (pin "1") (pinfunction "1_1") (pintype "passive"))
      (node (ref "C132") (pin "1") (pinfunction "1_1") (pintype "passive"))
      (node (ref "C134") (pin "1") (pinfunction "1_1") (pintype "passive"))
      (node (ref "C136") (pin "2") (pinfunction "2_2") (pintype "passive"))
      (node (ref "C137") (pin "2") (pinfunction "2_2") (pintype "passive"))
      (node (ref "C138") (pin "2") (pinfunction "2_2") (pintype "passive"))
      (node (ref "C139") (pin "2") (pinfunction "2_2") (pintype "passive"))
      (node (ref "C140") (pin "1") (pinfunction "1_1") (pintype "passive"))
      (node (ref "C142") (pin "1") (pinfunction "1_1") (pintype "passive"))
      (node (ref "C144") (pin "1") (pinfunction "1_1") (pintype "passive"))
      (node (ref "C145") (pin "1") (pinfunction "1_1") (pintype "passive"))
      (node (ref "C146") (pin "1") (pinfunction "1_1") (pintype "passive"))
      (node (ref "C147") (pin "1") (pinfunction "1_1") (pintype "passive"))
      (node (ref "C148") (pin "1") (pinfunction "1_1") (pintype "passive"))
      (node (ref "C149") (pin "1") (pinfunction "1_1") (pintype "passive"))
      (node (ref "C150") (pin "1") (pinfunction "1_1") (pintype "passive"))
      (node (ref "C152") (pin "2") (pinfunction "2_2") (pintype "passive"))
      (node (ref "C153") (pin "1") (pinfunction "1_1") (pintype "passive"))
      (node (ref "C154") (pin "1") (pinfunction "1_1") (pintype "passive"))
      (node (ref "C155") (pin "2") (pinfunction "2_2") (pintype "passive"))
      (node (ref "C156") (pin "2") (pinfunction "2_2") (pintype "passive"))
      (node (ref "C157") (pin "2") (pinfunction "2_2") (pintype "passive"))
      (node (ref "C158") (pin "2") (pinfunction "2_2") (pintype "passive"))
      (node (ref "C159") (pin "2") (pinfunction "2_2") (pintype "passive"))
      (node (ref "C160") (pin "2") (pinfunction "2_2") (pintype "passive"))
      (node (ref "C161") (pin "2") (pinfunction "2_2") (pintype "passive"))
      (node (ref "C162") (pin "2") (pinfunction "2_2") (pintype "passive"))
      (node (ref "C163") (pin "2") (pinfunction "2_2") (pintype "passive"))
      (node (ref "C164") (pin "2") (pinfunction "2_2") (pintype "passive"))
      (node (ref "C165") (pin "2") (pinfunction "2_2") (pintype "passive"))
      (node (ref "C166") (pin "2") (pinfunction "2_2") (pintype "passive"))
      (node (ref "C167") (pin "2") (pinfunction "2_2") (pintype "passive"))
      (node (ref "C168") (pin "1") (pinfunction "1_1") (pintype "passive"))
      (node (ref "C76") (pin "1") (pinfunction "1_1") (pintype "passive"))
      (node (ref "C77") (pin "1") (pinfunction "1_1") (pintype "passive"))
      (node (ref "C78") (pin "1") (pinfunction "1_1") (pintype "passive"))
      (node (ref "C79") (pin "1") (pinfunction "1_1") (pintype "passive"))
      (node (ref "C80") (pin "1") (pinfunction "1_1") (pintype "passive"))
      (node (ref "C81") (pin "1") (pinfunction "1_1") (pintype "passive"))
      (node (ref "C82") (pin "1") (pinfunction "1_1") (pintype "passive"))
      (node (ref "C83") (pin "1") (pinfunction "1_1") (pintype "passive"))
      (node (ref "C84") (pin "1") (pinfunction "1_1") (pintype "passive"))
      (node (ref "C85") (pin "1") (pinfunction "1_1") (pintype "passive"))
      (node (ref "C86") (pin "1") (pinfunction "1_1") (pintype "passive"))
      (node (ref "C88") (pin "1") (pinfunction "1_1") (pintype "passive"))
      (node (ref "C89") (pin "1") (pinfunction "1_1") (pintype "passive"))
      (node (ref "C91") (pin "1") (pinfunction "1_1") (pintype "passive"))
      (node (ref "C92") (pin "1") (pinfunction "1_1") (pintype "passive"))
      (node (ref "C94") (pin "1") (pinfunction "1_1") (pintype "passive"))
      (node (ref "C95") (pin "1") (pinfunction "1_1") (pintype "passive"))
      (node (ref "C97") (pin "1") (pinfunction "1_1") (pintype "passive"))
      (node (ref "C98") (pin "1") (pinfunction "1_1") (pintype "passive"))
      (node (ref "C99") (pin "1") (pinfunction "1_1") (pintype "passive"))
      (node (ref "M1") (pin "2") (pinfunction "2_2") (pintype "passive"))
      (node (ref "M1") (pin "3") (pinfunction "3_3") (pintype "passive"))
      (node (ref "M2") (pin "2") (pinfunction "2_2") (pintype "passive"))
      (node (ref "M2") (pin "3") (pinfunction "3_3") (pintype "passive"))
      (node (ref "R57") (pin "1") (pinfunction "1_1") (pintype "passive"))
      (node (ref "R58") (pin "1") (pinfunction "1_1") (pintype "passive"))
      (node (ref "R61") (pin "1") (pinfunction "1_1") (pintype "passive"))
      (node (ref "R63") (pin "1") (pinfunction "1_1") (pintype "passive"))
      (node (ref "R64") (pin "1") (pinfunction "1_1") (pintype "passive"))
      (node (ref "R65") (pin "1") (pinfunction "1_1") (pintype "passive"))
      (node (ref "R74") (pin "1") (pinfunction "1_1") (pintype "passive"))
      (node (ref "R79") (pin "1") (pinfunction "1_1") (pintype "passive"))
      (node (ref "R81") (pin "1") (pinfunction "1_1") (pintype "passive"))
      (node (ref "S1") (pin "1") (pinfunction "1_1") (pintype "passive"))
      (node (ref "S1") (pin "4") (pinfunction "4_4") (pintype "passive"))
      (node (ref "S1") (pin "7") (pinfunction "7_7") (pintype "passive"))
      (node (ref "S2") (pin "1") (pinfunction "1_1") (pintype "passive"))
      (node (ref "S2") (pin "4") (pinfunction "4_4") (pintype "passive"))
      (node (ref "S2") (pin "7") (pinfunction "7_7") (pintype "passive"))
      (node (ref "U18") (pin "44") (pinfunction "VSS_44") (pintype "power_in"))
      (node (ref "U18") (pin "58") (pinfunction "VSS_58") (pintype "power_in"))
      (node (ref "U18") (pin "65") (pinfunction "EXP_VSS_65") (pintype "power_in"))
      (node (ref "U19") (pin "49") (pinfunction "GND_49") (pintype "power_in"))
      (node (ref "U20") (pin "44") (pinfunction "VSS_44") (pintype "power_in"))
      (node (ref "U20") (pin "58") (pinfunction "VSS_58") (pintype "power_in"))
      (node (ref "U20") (pin "65") (pinfunction "EXP_VSS_65") (pintype "power_in"))
      (node (ref "U21") (pin "4") (pinfunction "VSS_4") (pintype "power_in"))
      (node (ref "U22") (pin "4") (pinfunction "GND_4") (pintype "power_in"))
      (node (ref "U23") (pin "4") (pinfunction "VSS_4") (pintype "power_in"))
      (node (ref "U24") (pin "4") (pinfunction "GND_4") (pintype "power_in"))
      (node (ref "U25") (pin "3") (pinfunction "GND_3") (pintype "power_in"))
      (node (ref "U26") (pin "3") (pinfunction "3_3") (pintype "passive"))
      (node (ref "Y4") (pin "2") (pinfunction "GND_2") (pintype "power_in"))
      (node (ref "Y4") (pin "4") (pinfunction "GND_4") (pintype "power_in"))
      (node (ref "Y5") (pin "2") (pinfunction "GND_2") (pintype "power_in"))
      (node (ref "Y5") (pin "4") (pinfunction "GND_4") (pintype "power_in"))
      (node (ref "Y6") (pin "2") (pinfunction "GND_2") (pintype "power_in"))
      (node (ref "Y6") (pin "4") (pinfunction "GND_4") (pintype "power_in"))
    )
    (net (code "19") (name "Net-(FB26-Pad2)") (class "Default")
      (node (ref "FB26") (pin "2") (pinfunction "2_2") (pintype "passive"))
      (node (ref "M1") (pin "1") (pinfunction "1_1") (pintype "passive"))
    )
    (net (code "20") (name "Net-(FB27-Pad2)") (class "Default")
      (node (ref "FB27") (pin "2") (pinfunction "2_2") (pintype "passive"))
      (node (ref "M1") (pin "4") (pinfunction "4_4") (pintype "passive"))
    )
    (net (code "21") (name "Net-(FB28-Pad2)") (class "Default")
      (node (ref "FB28") (pin "2") (pinfunction "2_2") (pintype "passive"))
      (node (ref "M2") (pin "1") (pinfunction "1_1") (pintype "passive"))
    )
    (net (code "22") (name "Net-(FB29-Pad2)") (class "Default")
      (node (ref "FB29") (pin "2") (pinfunction "2_2") (pintype "passive"))
      (node (ref "M2") (pin "4") (pinfunction "4_4") (pintype "passive"))
    )
    (net (code "23") (name "Net-(LED12-Anode)") (class "Default")
      (node (ref "LED12") (pin "2") (pinfunction "Anode_2") (pintype "passive"))
      (node (ref "R66") (pin "1") (pinfunction "1_1") (pintype "passive"))
    )
    (net (code "24") (name "Net-(LED12-Cathode)") (class "Default")
      (node (ref "LED12") (pin "1") (pinfunction "Cathode_1") (pintype "passive"))
      (node (ref "U18") (pin "2") (pinfunction "PWM0_2") (pintype "output"))
    )
    (net (code "25") (name "Net-(LED13-Anode)") (class "Default")
      (node (ref "LED13") (pin "2") (pinfunction "Anode_2") (pintype "passive"))
      (node (ref "R68") (pin "1") (pinfunction "1_1") (pintype "passive"))
    )
    (net (code "26") (name "Net-(LED13-Cathode)") (class "Default")
      (node (ref "LED13") (pin "1") (pinfunction "Cathode_1") (pintype "passive"))
      (node (ref "U18") (pin "3") (pinfunction "PWM1_3") (pintype "output"))
    )
    (net (code "27") (name "Net-(LED14-Anode)") (class "Default")
      (node (ref "LED14") (pin "2") (pinfunction "Anode_2") (pintype "passive"))
      (node (ref "R82") (pin "1") (pinfunction "1_1") (pintype "passive"))
    )
    (net (code "28") (name "Net-(LED14-Cathode)") (class "Default")
      (node (ref "LED14") (pin "1") (pinfunction "Cathode_1") (pintype "passive"))
      (node (ref "U20") (pin "2") (pinfunction "PWM0_2") (pintype "output"))
    )
    (net (code "29") (name "Net-(LED15-Anode)") (class "Default")
      (node (ref "LED15") (pin "2") (pinfunction "Anode_2") (pintype "passive"))
      (node (ref "R83") (pin "1") (pinfunction "1_1") (pintype "passive"))
    )
    (net (code "30") (name "Net-(LED15-Cathode)") (class "Default")
      (node (ref "LED15") (pin "1") (pinfunction "Cathode_1") (pintype "passive"))
      (node (ref "U20") (pin "3") (pinfunction "PWM1_3") (pintype "output"))
    )
    (net (code "31") (name "Net-(R84-Pad1)") (class "Default")
      (node (ref "R84") (pin "1") (pinfunction "1_1") (pintype "passive"))
      (node (ref "U26") (pin "4") (pinfunction "4_4") (pintype "passive"))
    )
    (net (code "32") (name "Net-(R85-Pad1)") (class "Default")
      (node (ref "R85") (pin "1") (pinfunction "1_1") (pintype "passive"))
      (node (ref "U26") (pin "1") (pinfunction "1_1") (pintype "passive"))
    )
    (net (code "33") (name "Net-(U18-FREQSEL0)") (class "Default")
      (node (ref "R55") (pin "2") (pinfunction "2_2") (pintype "passive"))
      (node (ref "U18") (pin "30") (pinfunction "FREQSEL0_30") (pintype "input"))
    )
    (net (code "34") (name "Net-(U18-FREQSEL1)") (class "Default")
      (node (ref "R56") (pin "2") (pinfunction "2_2") (pintype "passive"))
      (node (ref "U18") (pin "31") (pinfunction "FREQSEL1_31") (pintype "input"))
    )
    (net (code "35") (name "Net-(U18-SATA_RXM)") (class "Default")
      (node (ref "C93") (pin "1") (pinfunction "1_1") (pintype "passive"))
      (node (ref "U18") (pin "59") (pinfunction "SATA_RXM_59") (pintype "input"))
    )
    (net (code "36") (name "Net-(U18-SATA_RXP)") (class "Default")
      (node (ref "C87") (pin "1") (pinfunction "1_1") (pintype "passive"))
      (node (ref "U18") (pin "60") (pinfunction "SATA_RXP_60") (pintype "input"))
    )
    (net (code "37") (name "Net-(U18-SATA_TXM)") (class "Default")
      (node (ref "C96") (pin "1") (pinfunction "1_1") (pintype "passive"))
      (node (ref "U18") (pin "56") (pinfunction "SATA_TXM_56") (pintype "output"))
    )
    (net (code "38") (name "Net-(U18-SATA_TXP)") (class "Default")
      (node (ref "C90") (pin "1") (pinfunction "1_1") (pintype "passive"))
      (node (ref "U18") (pin "57") (pinfunction "SATA_TXP_57") (pintype "output"))
    )
    (net (code "39") (name "Net-(U18-USB_R1)") (class "Default")
      (node (ref "R62") (pin "2") (pinfunction "2_2") (pintype "passive"))
      (node (ref "U18") (pin "38") (pinfunction "USB_R1_38") (pintype "output"))
    )
    (net (code "40") (name "Net-(U18-USB_R1RTN)") (class "Default")
      (node (ref "R62") (pin "1") (pinfunction "1_1") (pintype "passive"))
      (node (ref "U18") (pin "39") (pinfunction "USB_R1RTN_39") (pintype "input"))
    )
    (net (code "41") (name "Net-(U18-USB_VBUS)") (class "Default")
      (node (ref "R60") (pin "2") (pinfunction "2_2") (pintype "passive"))
      (node (ref "R61") (pin "2") (pinfunction "2_2") (pintype "passive"))
      (node (ref "U18") (pin "50") (pinfunction "USB_VBUS_50") (pintype "input"))
    )
    (net (code "42") (name "Net-(U18-XI)") (class "Default")
      (node (ref "U18") (pin "52") (pinfunction "XI_52") (pintype "input"))
      (node (ref "Y4") (pin "3") (pintype "passive"))
    )
    (net (code "43") (name "Net-(U18-XO)") (class "Default")
      (node (ref "U18") (pin "54") (pinfunction "XO_54") (pintype "output"))
      (node (ref "Y4") (pin "1") (pintype "passive"))
    )
    (net (code "44") (name "Net-(U19-GANGED{slash}SMBA2{slash}HS_UP)") (class "Default")
      (node (ref "R64") (pin "2") (pinfunction "2_2") (pintype "passive"))
      (node (ref "U19") (pin "35") (pinfunction "GANGED/SMBA2/HS_UP_35") (pintype "input"))
    )
    (net (code "45") (name "Net-(U19-GRSTZ)") (class "Default")
      (node (ref "C77") (pin "2") (pinfunction "2_2") (pintype "passive"))
      (node (ref "U19") (pin "11") (pinfunction "GRSTZ_11") (pintype "input"))
    )
    (net (code "46") (name "Net-(U19-PWRCRL_POL{slash}SS_DN1)") (class "Default")
      (node (ref "R63") (pin "2") (pinfunction "2_2") (pintype "passive"))
      (node (ref "U19") (pin "21") (pinfunction "PWRCRL_POL/SS_DN1_21") (pintype "bidirectional"))
    )
    (net (code "47") (name "Net-(U19-TEST)") (class "Default")
      (node (ref "R65") (pin "2") (pinfunction "2_2") (pintype "passive"))
      (node (ref "U19") (pin "10") (pinfunction "TEST_10") (pintype "input"))
    )
    (net (code "48") (name "Net-(U19-USB_R1)") (class "Default")
      (node (ref "R57") (pin "2") (pinfunction "2_2") (pintype "passive"))
      (node (ref "U19") (pin "24") (pinfunction "USB_R1_24") (pintype "input"))
    )
    (net (code "49") (name "Net-(U19-USB_SSRXM_DN1)") (class "Default")
      (node (ref "C106") (pin "1") (pinfunction "1_1") (pintype "passive"))
      (node (ref "U19") (pin "47") (pinfunction "USB_SSRXM_DN1_47") (pintype "input"))
    )
    (net (code "50") (name "Net-(U19-USB_SSRXM_DN2)") (class "Default")
      (node (ref "C116") (pin "1") (pinfunction "1_1") (pintype "passive"))
      (node (ref "U19") (pin "20") (pinfunction "USB_SSRXM_DN2_20") (pintype "input"))
    )
    (net (code "51") (name "Net-(U19-USB_SSRXP_DN1)") (class "Default")
      (node (ref "C101") (pin "1") (pinfunction "1_1") (pintype "passive"))
      (node (ref "U19") (pin "46") (pinfunction "USB_SSRXP_DN1_46") (pintype "input"))
    )
    (net (code "52") (name "Net-(U19-USB_SSRXP_DN2)") (class "Default")
      (node (ref "C113") (pin "1") (pinfunction "1_1") (pintype "passive"))
      (node (ref "U19") (pin "19") (pinfunction "USB_SSRXP_DN2_19") (pintype "input"))
    )
    (net (code "53") (name "Net-(U19-USB_SSTXM_DN1)") (class "Default")
      (node (ref "C120") (pin "2") (pinfunction "2_2") (pintype "passive"))
      (node (ref "U19") (pin "44") (pinfunction "USB_SSTXM_DN1_44") (pintype "output"))
    )
    (net (code "54") (name "Net-(U19-USB_SSTXM_DN2)") (class "Default")
      (node (ref "C122") (pin "2") (pinfunction "2_2") (pintype "passive"))
      (node (ref "U19") (pin "17") (pinfunction "USB_SSTXM_DN2_17") (pintype "output"))
    )
    (net (code "55") (name "Net-(U19-USB_SSTXM_UP)") (class "Default")
      (node (ref "C118") (pin "2") (pinfunction "2_2") (pintype "passive"))
      (node (ref "U19") (pin "28") (pinfunction "USB_SSTXM_UP_28") (pintype "output"))
    )
    (net (code "56") (name "Net-(U19-USB_SSTXP_DN1)") (class "Default")
      (node (ref "C119") (pin "2") (pinfunction "2_2") (pintype "passive"))
      (node (ref "U19") (pin "43") (pinfunction "USB_SSTXP_DN1_43") (pintype "output"))
    )
    (net (code "57") (name "Net-(U19-USB_SSTXP_DN2)") (class "Default")
      (node (ref "C121") (pin "2") (pinfunction "2_2") (pintype "passive"))
      (node (ref "U19") (pin "16") (pinfunction "USB_SSTXP_DN2_16") (pintype "output"))
    )
    (net (code "58") (name "Net-(U19-USB_SSTXP_UP)") (class "Default")
      (node (ref "C117") (pin "2") (pinfunction "2_2") (pintype "passive"))
      (node (ref "U19") (pin "29") (pinfunction "USB_SSTXP_UP_29") (pintype "output"))
    )
    (net (code "59") (name "Net-(U19-USB_VBUS)") (class "Default")
      (node (ref "R58") (pin "2") (pinfunction "2_2") (pintype "passive"))
      (node (ref "R59") (pin "2") (pinfunction "2_2") (pintype "passive"))
      (node (ref "U19") (pin "9") (pinfunction "USB_VBUS_9") (pintype "input"))
    )
    (net (code "60") (name "Net-(U19-XI)") (class "Default")
      (node (ref "C123") (pin "2") (pinfunction "2_2") (pintype "passive"))
      (node (ref "R67") (pin "1") (pinfunction "1_1") (pintype "passive"))
      (node (ref "U19") (pin "38") (pinfunction "XI_38") (pintype "input"))
      (node (ref "Y5") (pin "3") (pintype "passive"))
    )
    (net (code "61") (name "Net-(U19-XO)") (class "Default")
      (node (ref "C124") (pin "2") (pinfunction "2_2") (pintype "passive"))
      (node (ref "R67") (pin "2") (pinfunction "2_2") (pintype "passive"))
      (node (ref "U19") (pin "39") (pinfunction "XO_39") (pintype "output"))
      (node (ref "Y5") (pin "1") (pintype "passive"))
    )
    (net (code "62") (name "Net-(U20-FREQSEL0)") (class "Default")
      (node (ref "R69") (pin "2") (pinfunction "2_2") (pintype "passive"))
      (node (ref "U20") (pin "30") (pinfunction "FREQSEL0_30") (pintype "input"))
    )
    (net (code "63") (name "Net-(U20-FREQSEL1)") (class "Default")
      (node (ref "R70") (pin "2") (pinfunction "2_2") (pintype "passive"))
      (node (ref "U20") (pin "31") (pinfunction "FREQSEL1_31") (pintype "input"))
    )
    (net (code "64") (name "Net-(U20-SATA_RXM)") (class "Default")
      (node (ref "C141") (pin "1") (pinfunction "1_1") (pintype "passive"))
      (node (ref "U20") (pin "59") (pinfunction "SATA_RXM_59") (pintype "input"))
    )
    (net (code "65") (name "Net-(U20-SATA_RXP)") (class "Default")
      (node (ref "C133") (pin "1") (pinfunction "1_1") (pintype "passive"))
      (node (ref "U20") (pin "60") (pinfunction "SATA_RXP_60") (pintype "input"))
    )
    (net (code "66") (name "Net-(U20-SATA_TXM)") (class "Default")
      (node (ref "C143") (pin "1") (pinfunction "1_1") (pintype "passive"))
      (node (ref "U20") (pin "56") (pinfunction "SATA_TXM_56") (pintype "output"))
    )
    (net (code "67") (name "Net-(U20-SATA_TXP)") (class "Default")
      (node (ref "C135") (pin "1") (pinfunction "1_1") (pintype "passive"))
      (node (ref "U20") (pin "57") (pinfunction "SATA_TXP_57") (pintype "output"))
    )
    (net (code "68") (name "Net-(U20-USB_R1)") (class "Default")
      (node (ref "R80") (pin "2") (pinfunction "2_2") (pintype "passive"))
      (node (ref "U20") (pin "38") (pinfunction "USB_R1_38") (pintype "output"))
    )
    (net (code "69") (name "Net-(U20-USB_R1RTN)") (class "Default")
      (node (ref "R80") (pin "1") (pinfunction "1_1") (pintype "passive"))
      (node (ref "U20") (pin "39") (pinfunction "USB_R1RTN_39") (pintype "input"))
    )
    (net (code "70") (name "Net-(U20-USB_VBUS)") (class "Default")
      (node (ref "R75") (pin "2") (pinfunction "2_2") (pintype "passive"))
      (node (ref "R79") (pin "2") (pinfunction "2_2") (pintype "passive"))
      (node (ref "U20") (pin "50") (pinfunction "USB_VBUS_50") (pintype "input"))
    )
    (net (code "71") (name "Net-(U20-XI)") (class "Default")
      (node (ref "U20") (pin "52") (pinfunction "XI_52") (pintype "input"))
      (node (ref "Y6") (pin "3") (pintype "passive"))
    )
    (net (code "72") (name "Net-(U20-XO)") (class "Default")
      (node (ref "U20") (pin "54") (pinfunction "XO_54") (pintype "output"))
      (node (ref "Y6") (pin "1") (pintype "passive"))
    )
    (net (code "73") (name "Net-(U21-*HOLD)") (class "Default")
      (node (ref "R72") (pin "2") (pinfunction "2_2") (pintype "passive"))
      (node (ref "U21") (pin "7") (pinfunction "*HOLD_7") (pintype "passive"))
    )
    (net (code "74") (name "Net-(U21-*WP)") (class "Default")
      (node (ref "R71") (pin "2") (pinfunction "2_2") (pintype "passive"))
      (node (ref "U21") (pin "3") (pinfunction "*WP_3") (pintype "passive"))
    )
    (net (code "75") (name "Net-(U22-BST)") (class "Default")
      (node (ref "C128") (pin "1") (pinfunction "1_1") (pintype "passive"))
      (node (ref "U22") (pin "6") (pinfunction "BST_6") (pintype "passive"))
    )
    (net (code "76") (name "Net-(U22-FB)") (class "Default")
      (node (ref "R73") (pin "2") (pinfunction "2_2") (pintype "passive"))
      (node (ref "R74") (pin "2") (pinfunction "2_2") (pintype "passive"))
      (node (ref "U22") (pin "1") (pinfunction "FB_1") (pintype "passive"))
    )
    (net (code "77") (name "Net-(U22-SW)") (class "Default")
      (node (ref "C128") (pin "2") (pinfunction "2_2") (pintype "passive"))
      (node (ref "L9") (pin "1") (pinfunction "1_1") (pintype "passive"))
      (node (ref "U22") (pin "5") (pinfunction "SW_5") (pintype "passive"))
    )
    (net (code "78") (name "Net-(U23-*HOLD)") (class "Default")
      (node (ref "R77") (pin "2") (pinfunction "2_2") (pintype "passive"))
      (node (ref "U23") (pin "7") (pinfunction "*HOLD_7") (pintype "passive"))
    )
    (net (code "79") (name "Net-(U23-*WP)") (class "Default")
      (node (ref "R76") (pin "2") (pinfunction "2_2") (pintype "passive"))
      (node (ref "U23") (pin "3") (pinfunction "*WP_3") (pintype "passive"))
    )
    (net (code "80") (name "Net-(U24-BST)") (class "Default")
      (node (ref "C151") (pin "1") (pinfunction "1_1") (pintype "passive"))
      (node (ref "U24") (pin "6") (pinfunction "BST_6") (pintype "passive"))
    )
    (net (code "81") (name "Net-(U24-FB)") (class "Default")
      (node (ref "R78") (pin "2") (pinfunction "2_2") (pintype "passive"))
      (node (ref "R81") (pin "2") (pinfunction "2_2") (pintype "passive"))
      (node (ref "U24") (pin "1") (pinfunction "FB_1") (pintype "passive"))
    )
    (net (code "82") (name "Net-(U24-SW)") (class "Default")
      (node (ref "C151") (pin "2") (pinfunction "2_2") (pintype "passive"))
      (node (ref "L10") (pin "1") (pinfunction "1_1") (pintype "passive"))
      (node (ref "U24") (pin "5") (pinfunction "SW_5") (pintype "passive"))
    )
    (net (code "83") (name "Net-(U25-CT)") (class "Default")
      (node (ref "C167") (pin "1") (pinfunction "1_1") (pintype "passive"))
      (node (ref "U25") (pin "5") (pinfunction "CT_5") (pintype "input"))
    )
    (net (code "84") (name "Net-(U25-RST_N)") (class "Default")
      (node (ref "U25") (pin "1") (pinfunction "RST_N_1") (pintype "open_collector"))
      (node (ref "U26") (pin "2") (pinfunction "2_2") (pintype "passive"))
    )
    (net (code "85") (name "S1_RX_N") (class "Default")
      (node (ref "C93") (pin "2") (pinfunction "2_2") (pintype "passive"))
      (node (ref "S1") (pin "5") (pinfunction "5_5") (pintype "passive"))
    )
    (net (code "86") (name "S1_RX_P") (class "Default")
      (node (ref "C87") (pin "2") (pinfunction "2_2") (pintype "passive"))
      (node (ref "S1") (pin "6") (pinfunction "6_6") (pintype "passive"))
    )
    (net (code "87") (name "S1_TX_N") (class "Default")
      (node (ref "C96") (pin "2") (pinfunction "2_2") (pintype "passive"))
      (node (ref "S1") (pin "3") (pinfunction "3_3") (pintype "passive"))
    )
    (net (code "88") (name "S1_TX_P") (class "Default")
      (node (ref "C90") (pin "2") (pinfunction "2_2") (pintype "passive"))
      (node (ref "S1") (pin "2") (pinfunction "2_2") (pintype "passive"))
    )
    (net (code "89") (name "S2_RX_N") (class "Default")
      (node (ref "C141") (pin "2") (pinfunction "2_2") (pintype "passive"))
      (node (ref "S2") (pin "5") (pinfunction "5_5") (pintype "passive"))
    )
    (net (code "90") (name "S2_RX_P") (class "Default")
      (node (ref "C133") (pin "2") (pinfunction "2_2") (pintype "passive"))
      (node (ref "S2") (pin "6") (pinfunction "6_6") (pintype "passive"))
    )
    (net (code "91") (name "S2_TX_N") (class "Default")
      (node (ref "C143") (pin "2") (pinfunction "2_2") (pintype "passive"))
      (node (ref "S2") (pin "3") (pinfunction "3_3") (pintype "passive"))
    )
    (net (code "92") (name "S2_TX_P") (class "Default")
      (node (ref "C135") (pin "2") (pinfunction "2_2") (pintype "passive"))
      (node (ref "S2") (pin "2") (pinfunction "2_2") (pintype "passive"))
    )
    (net (code "93") (name "SPI_CE_A") (class "Default")
      (node (ref "U18") (pin "21") (pinfunction "SPI_CS0_21") (pintype "output"))
      (node (ref "U21") (pin "1") (pinfunction "*CS_1") (pintype "passive"))
    )
    (net (code "94") (name "SPI_CE_B") (class "Default")
      (node (ref "U20") (pin "21") (pinfunction "SPI_CS0_21") (pintype "output"))
      (node (ref "U23") (pin "1") (pinfunction "*CS_1") (pintype "passive"))
    )
    (net (code "95") (name "SPI_SCK_A") (class "Default")
      (node (ref "U18") (pin "17") (pinfunction "SPI_SCLK_17") (pintype "output"))
      (node (ref "U21") (pin "6") (pinfunction "SCK_6") (pintype "bidirectional"))
    )
    (net (code "96") (name "SPI_SCK_B") (class "Default")
      (node (ref "U20") (pin "17") (pinfunction "SPI_SCLK_17") (pintype "output"))
      (node (ref "U23") (pin "6") (pinfunction "SCK_6") (pintype "bidirectional"))
    )
    (net (code "97") (name "SPI_SI_A") (class "Default")
      (node (ref "U18") (pin "20") (pinfunction "SPI_DATA_IN_20") (pintype "input"))
      (node (ref "U21") (pin "2") (pinfunction "SO_2") (pintype "output"))
    )
    (net (code "98") (name "SPI_SI_B") (class "Default")
      (node (ref "U20") (pin "20") (pinfunction "SPI_DATA_IN_20") (pintype "input"))
      (node (ref "U23") (pin "2") (pinfunction "SO_2") (pintype "output"))
    )
    (net (code "99") (name "SPI_SO_A") (class "Default")
      (node (ref "U18") (pin "18") (pinfunction "SPI_DATA_OUT_18") (pintype "output"))
      (node (ref "U21") (pin "5") (pinfunction "SI_5") (pintype "input"))
    )
    (net (code "100") (name "SPI_SO_B") (class "Default")
      (node (ref "U20") (pin "18") (pinfunction "SPI_DATA_OUT_18") (pintype "output"))
      (node (ref "U23") (pin "5") (pinfunction "SI_5") (pintype "input"))
    )
    (net (code "101") (name "S_RST") (class "Default")
      (node (ref "C168") (pin "2") (pinfunction "2_2") (pintype "passive"))
      (node (ref "R84") (pin "2") (pinfunction "2_2") (pintype "passive"))
      (node (ref "R86") (pin "2") (pinfunction "2_2") (pintype "passive"))
      (node (ref "U18") (pin "4") (pinfunction "GRSTZ_4") (pintype "input"))
      (node (ref "U20") (pin "4") (pinfunction "GRSTZ_4") (pintype "input"))
    )
    (net (code "102") (name "USB3-0-D_N") (class "Default")
      (node (ref "U19") (pin "27") (pinfunction "USB_DM_UP_27") (pintype "bidirectional"))
    )
    (net (code "103") (name "USB3-0-D_P") (class "Default")
      (node (ref "U19") (pin "26") (pinfunction "USB_DP_UP_26") (pintype "bidirectional"))
    )
    (net (code "104") (name "USB3-0-RX_N") (class "Default")
      (node (ref "C118") (pin "1") (pinfunction "1_1") (pintype "passive"))
    )
    (net (code "105") (name "USB3-0-RX_P") (class "Default")
      (node (ref "C117") (pin "1") (pinfunction "1_1") (pintype "passive"))
    )
    (net (code "106") (name "USB3-0-TX_N") (class "Default")
      (node (ref "U19") (pin "31") (pinfunction "USB_SSRXM_UP_31") (pintype "input"))
    )
    (net (code "107") (name "USB3-0-TX_P") (class "Default")
      (node (ref "U19") (pin "32") (pinfunction "USB_SSRXP_UP_32") (pintype "input"))
    )
    (net (code "108") (name "unconnected-(U18-GPIO0-Pad8)") (class "Default")
      (node (ref "U18") (pin "8") (pinfunction "GPIO0_8") (pintype "bidirectional"))
    )
    (net (code "109") (name "unconnected-(U18-GPIO1-Pad9)") (class "Default")
      (node (ref "U18") (pin "9") (pinfunction "GPIO1_9") (pintype "bidirectional"))
    )
    (net (code "110") (name "unconnected-(U18-GPIO2-Pad10)") (class "Default")
      (node (ref "U18") (pin "10") (pinfunction "GPIO2_10") (pintype "bidirectional"))
    )
    (net (code "111") (name "unconnected-(U18-GPIO3-Pad11)") (class "Default")
      (node (ref "U18") (pin "11") (pinfunction "GPIO3_11") (pintype "bidirectional"))
    )
    (net (code "112") (name "unconnected-(U18-GPIO4-Pad13)") (class "Default")
      (node (ref "U18") (pin "13") (pinfunction "GPIO4_13") (pintype "bidirectional"))
    )
    (net (code "113") (name "unconnected-(U18-GPIO5-Pad14)") (class "Default")
      (node (ref "U18") (pin "14") (pinfunction "GPIO5_14") (pintype "bidirectional"))
    )
    (net (code "114") (name "unconnected-(U18-GPIO6-Pad15)") (class "Default")
      (node (ref "U18") (pin "15") (pinfunction "GPIO6_15") (pintype "bidirectional"))
    )
    (net (code "115") (name "unconnected-(U18-GPIO7-Pad16)") (class "Default")
      (node (ref "U18") (pin "16") (pinfunction "GPIO7_16") (pintype "bidirectional"))
    )
    (net (code "116") (name "unconnected-(U18-GPIO8{slash}UART_RX-Pad5)") (class "Default")
      (node (ref "U18") (pin "5") (pinfunction "GPIO8/UART_RX_5") (pintype "bidirectional"))
    )
    (net (code "117") (name "unconnected-(U18-GPIO9{slash}UART_TX-Pad6)") (class "Default")
      (node (ref "U18") (pin "6") (pinfunction "GPIO9/UART_TX_6") (pintype "bidirectional"))
    )
    (net (code "118") (name "unconnected-(U18-JTAG_TCK-Pad25)") (class "Default")
      (node (ref "U18") (pin "25") (pinfunction "JTAG_TCK_25") (pintype "input"))
    )
    (net (code "119") (name "unconnected-(U18-JTAG_TDI-Pad26)") (class "Default")
      (node (ref "U18") (pin "26") (pinfunction "JTAG_TDI_26") (pintype "input"))
    )
    (net (code "120") (name "unconnected-(U18-JTAG_TDO-Pad27)") (class "Default")
      (node (ref "U18") (pin "27") (pinfunction "JTAG_TDO_27") (pintype "output"))
    )
    (net (code "121") (name "unconnected-(U18-JTAG_TMS-Pad28)") (class "Default")
      (node (ref "U18") (pin "28") (pinfunction "JTAG_TMS_28") (pintype "input"))
    )
    (net (code "122") (name "unconnected-(U18-JTAG_TRSTZ-Pad29)") (class "Default")
      (node (ref "U18") (pin "29") (pinfunction "JTAG_TRSTZ_29") (pintype "input"))
    )
    (net (code "123") (name "unconnected-(U18-SPI_CS1{slash}GPIO10-Pad22)") (class "Default")
      (node (ref "U18") (pin "22") (pinfunction "SPI_CS1/GPIO10_22") (pintype "bidirectional"))
    )
    (net (code "124") (name "unconnected-(U18-SPI_CS2{slash}GPIO11-Pad23)") (class "Default")
      (node (ref "U18") (pin "23") (pinfunction "SPI_CS2/GPIO11_23") (pintype "bidirectional"))
    )
    (net (code "125") (name "unconnected-(U18-VSSOSC-Pad53)") (class "Default")
      (node (ref "U18") (pin "53") (pinfunction "VSSOSC_53") (pintype "power_in"))
    )
    (net (code "126") (name "unconnected-(U19-FULLPWRMGMTZ{slash}SMBA1{slash}SS_UP-Pad36)") (class "Default")
      (node (ref "U19") (pin "36") (pinfunction "FULLPWRMGMTZ/SMBA1/SS_UP_36") (pintype "input"))
    )
    (net (code "127") (name "unconnected-(U19-OVERCUR1Z-Pad5)") (class "Default")
      (node (ref "U19") (pin "5") (pinfunction "OVERCUR1Z_5") (pintype "input"))
    )
    (net (code "128") (name "unconnected-(U19-OVERCUR2Z-Pad8)") (class "Default")
      (node (ref "U19") (pin "8") (pinfunction "OVERCUR2Z_8") (pintype "input"))
    )
    (net (code "129") (name "unconnected-(U19-PWRCTL1{slash}BATEN1-Pad4)") (class "Default")
      (node (ref "U19") (pin "4") (pinfunction "PWRCTL1/BATEN1_4") (pintype "bidirectional"))
    )
    (net (code "130") (name "unconnected-(U19-PWRCTL2{slash}BATEN2-Pad6)") (class "Default")
      (node (ref "U19") (pin "6") (pinfunction "PWRCTL2/BATEN2_6") (pintype "bidirectional"))
    )
    (net (code "131") (name "unconnected-(U19-SCL{slash}SMBCLK-Pad2)") (class "Default")
      (node (ref "U19") (pin "2") (pinfunction "SCL/SMBCLK_2") (pintype "bidirectional"))
    )
    (net (code "132") (name "unconnected-(U19-SDA{slash}SMBDAT-Pad3)") (class "Default")
      (node (ref "U19") (pin "3") (pinfunction "SDA/SMBDAT_3") (pintype "bidirectional"))
    )
    (net (code "133") (name "unconnected-(U19-SMBUSZ{slash}SS_DN2-Pad22)") (class "Default")
      (node (ref "U19") (pin "22") (pinfunction "SMBUSZ/SS_DN2_22") (pintype "input"))
    )
    (net (code "134") (name "unconnected-(U20-GPIO0-Pad8)") (class "Default")
      (node (ref "U20") (pin "8") (pinfunction "GPIO0_8") (pintype "bidirectional"))
    )
    (net (code "135") (name "unconnected-(U20-GPIO1-Pad9)") (class "Default")
      (node (ref "U20") (pin "9") (pinfunction "GPIO1_9") (pintype "bidirectional"))
    )
    (net (code "136") (name "unconnected-(U20-GPIO2-Pad10)") (class "Default")
      (node (ref "U20") (pin "10") (pinfunction "GPIO2_10") (pintype "bidirectional"))
    )
    (net (code "137") (name "unconnected-(U20-GPIO3-Pad11)") (class "Default")
      (node (ref "U20") (pin "11") (pinfunction "GPIO3_11") (pintype "bidirectional"))
    )
    (net (code "138") (name "unconnected-(U20-GPIO4-Pad13)") (class "Default")
      (node (ref "U20") (pin "13") (pinfunction "GPIO4_13") (pintype "bidirectional"))
    )
    (net (code "139") (name "unconnected-(U20-GPIO5-Pad14)") (class "Default")
      (node (ref "U20") (pin "14") (pinfunction "GPIO5_14") (pintype "bidirectional"))
    )
    (net (code "140") (name "unconnected-(U20-GPIO6-Pad15)") (class "Default")
      (node (ref "U20") (pin "15") (pinfunction "GPIO6_15") (pintype "bidirectional"))
    )
    (net (code "141") (name "unconnected-(U20-GPIO7-Pad16)") (class "Default")
      (node (ref "U20") (pin "16") (pinfunction "GPIO7_16") (pintype "bidirectional"))
    )
    (net (code "142") (name "unconnected-(U20-GPIO8{slash}UART_RX-Pad5)") (class "Default")
      (node (ref "U20") (pin "5") (pinfunction "GPIO8/UART_RX_5") (pintype "bidirectional"))
    )
    (net (code "143") (name "unconnected-(U20-GPIO9{slash}UART_TX-Pad6)") (class "Default")
      (node (ref "U20") (pin "6") (pinfunction "GPIO9/UART_TX_6") (pintype "bidirectional"))
    )
    (net (code "144") (name "unconnected-(U20-JTAG_TCK-Pad25)") (class "Default")
      (node (ref "U20") (pin "25") (pinfunction "JTAG_TCK_25") (pintype "input"))
    )
    (net (code "145") (name "unconnected-(U20-JTAG_TDI-Pad26)") (class "Default")
      (node (ref "U20") (pin "26") (pinfunction "JTAG_TDI_26") (pintype "input"))
    )
    (net (code "146") (name "unconnected-(U20-JTAG_TDO-Pad27)") (class "Default")
      (node (ref "U20") (pin "27") (pinfunction "JTAG_TDO_27") (pintype "output"))
    )
    (net (code "147") (name "unconnected-(U20-JTAG_TMS-Pad28)") (class "Default")
      (node (ref "U20") (pin "28") (pinfunction "JTAG_TMS_28") (pintype "input"))
    )
    (net (code "148") (name "unconnected-(U20-JTAG_TRSTZ-Pad29)") (class "Default")
      (node (ref "U20") (pin "29") (pinfunction "JTAG_TRSTZ_29") (pintype "input"))
    )
    (net (code "149") (name "unconnected-(U20-SPI_CS1{slash}GPIO10-Pad22)") (class "Default")
      (node (ref "U20") (pin "22") (pinfunction "SPI_CS1/GPIO10_22") (pintype "bidirectional"))
    )
    (net (code "150") (name "unconnected-(U20-SPI_CS2{slash}GPIO11-Pad23)") (class "Default")
      (node (ref "U20") (pin "23") (pinfunction "SPI_CS2/GPIO11_23") (pintype "bidirectional"))
    )
    (net (code "151") (name "unconnected-(U20-VSSOSC-Pad53)") (class "Default")
      (node (ref "U20") (pin "53") (pinfunction "VSSOSC_53") (pintype "power_in"))
    )
    (net (code "152") (name "unconnected-(U25-MR_N-Pad4)") (class "Default")
      (node (ref "U25") (pin "4") (pinfunction "MR_N_4") (pintype "input"))
    )
  )
)
